# octanis_v0_6.net
KiCad netlist of a schematic drawn in EAGLE
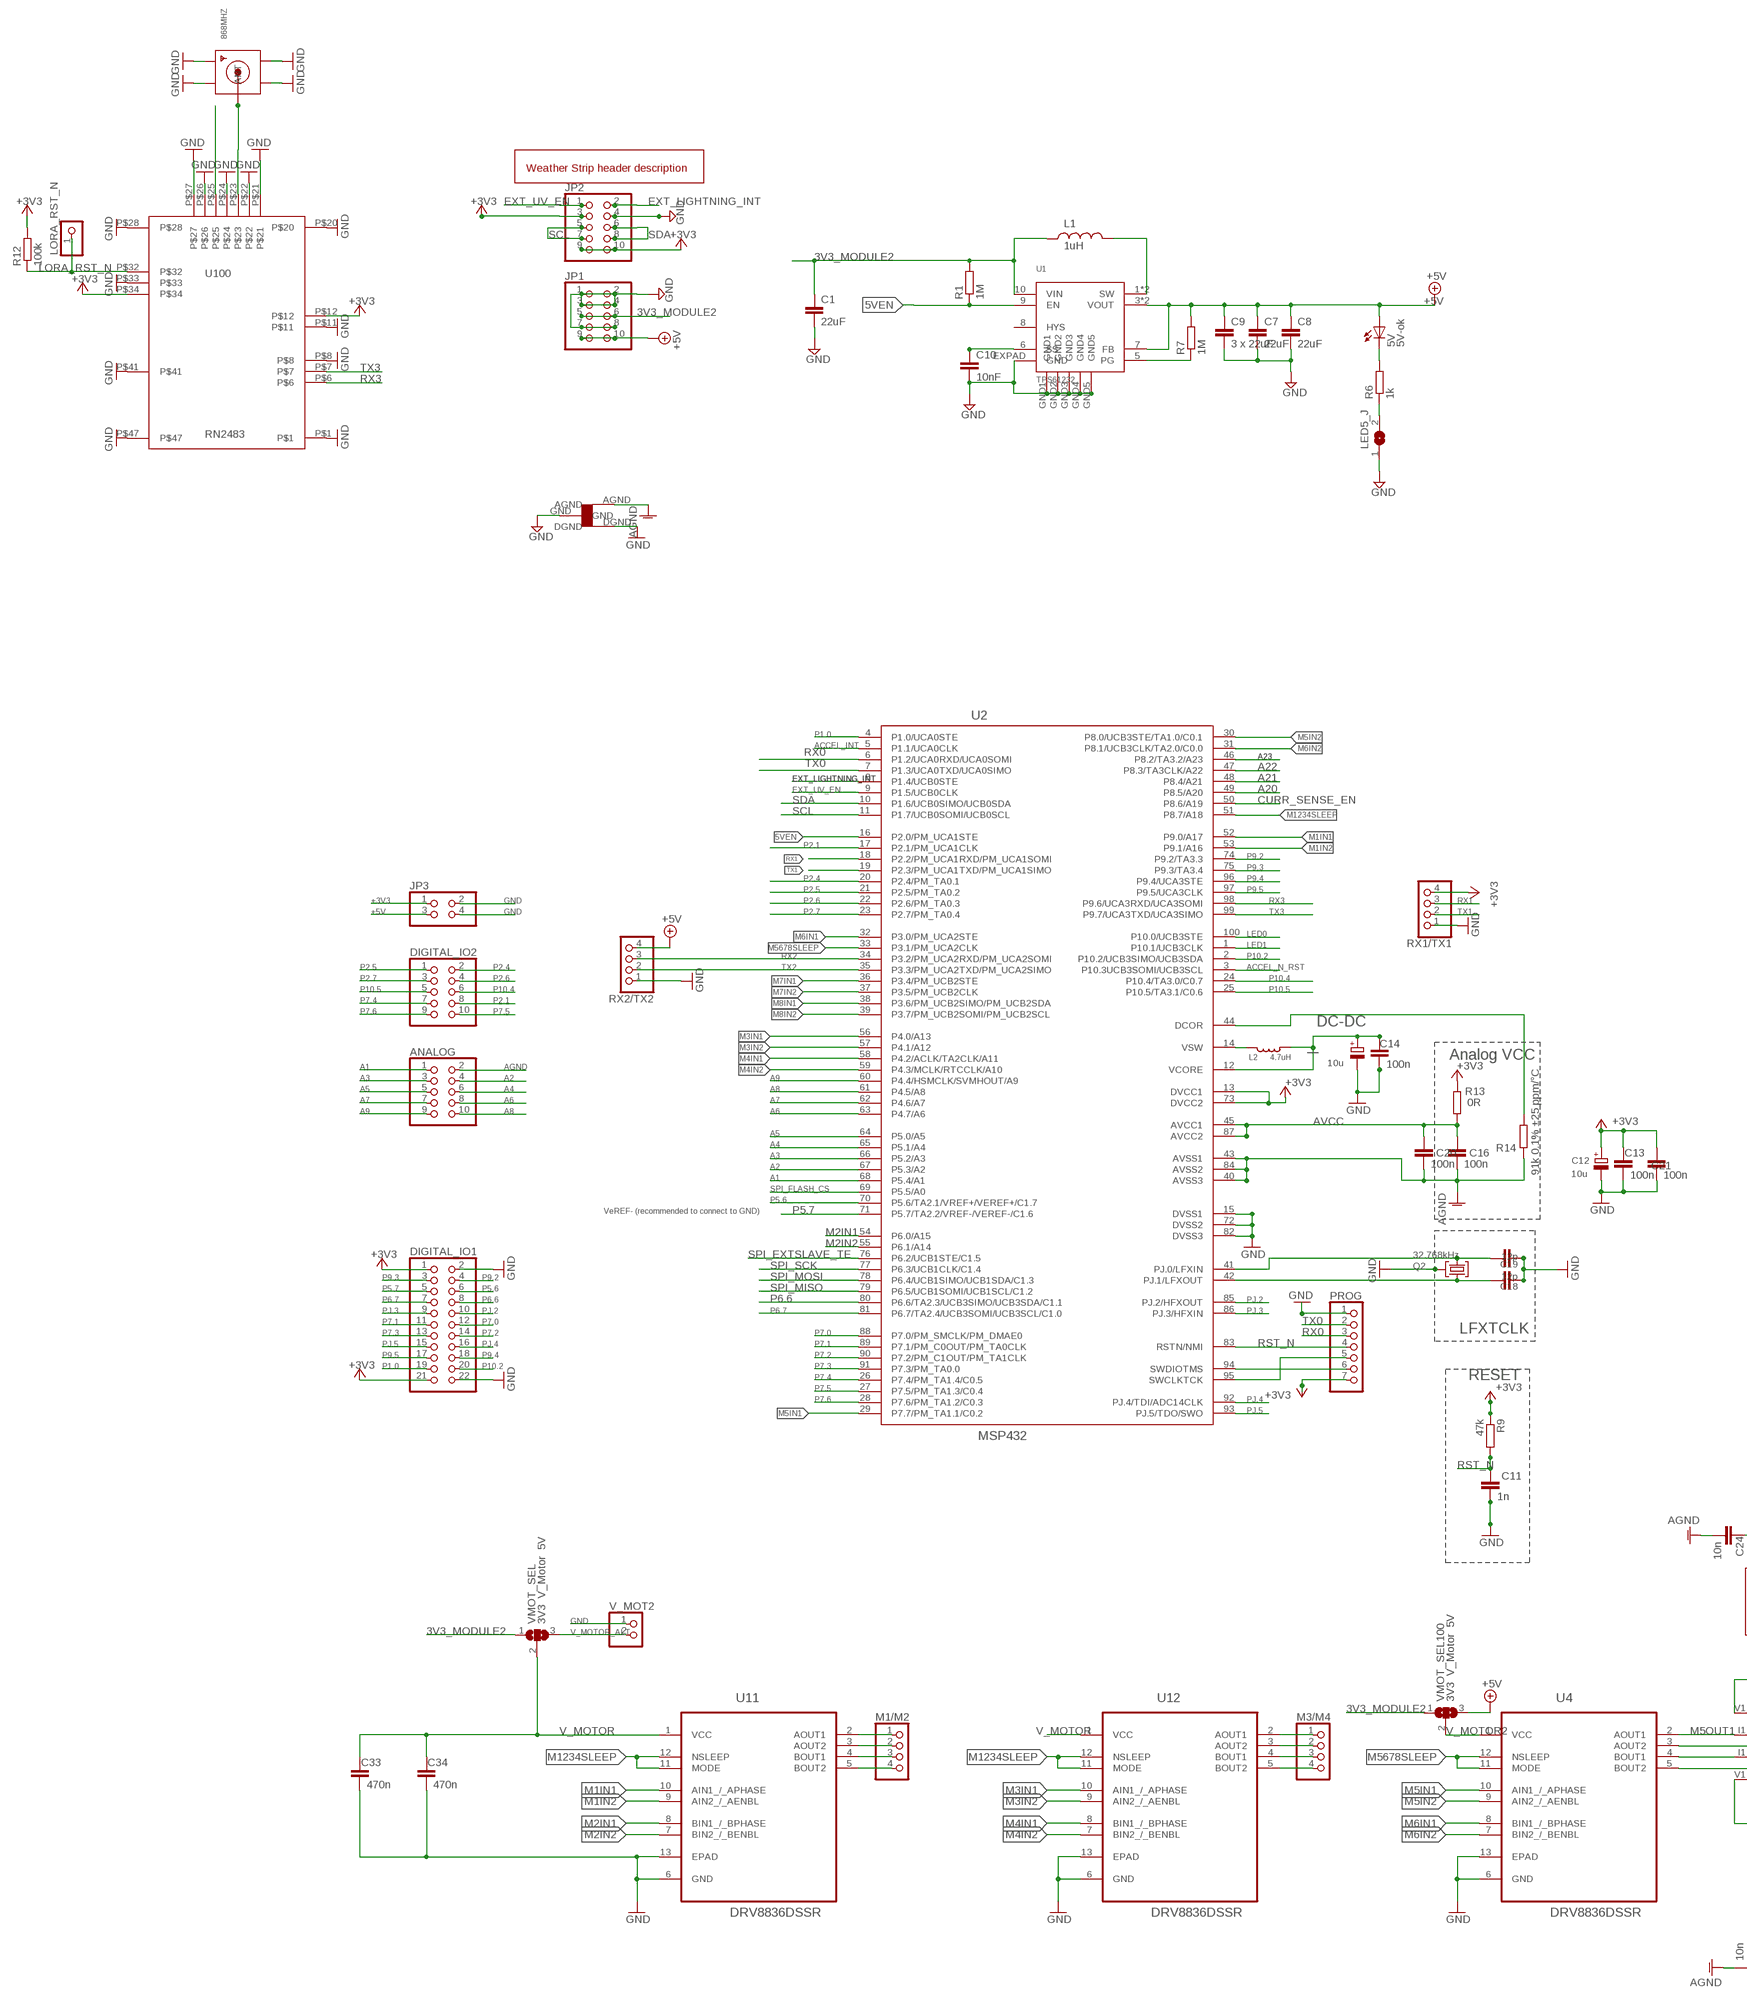
[diagram p0: schematic, sheet 1, part 1 of 2]
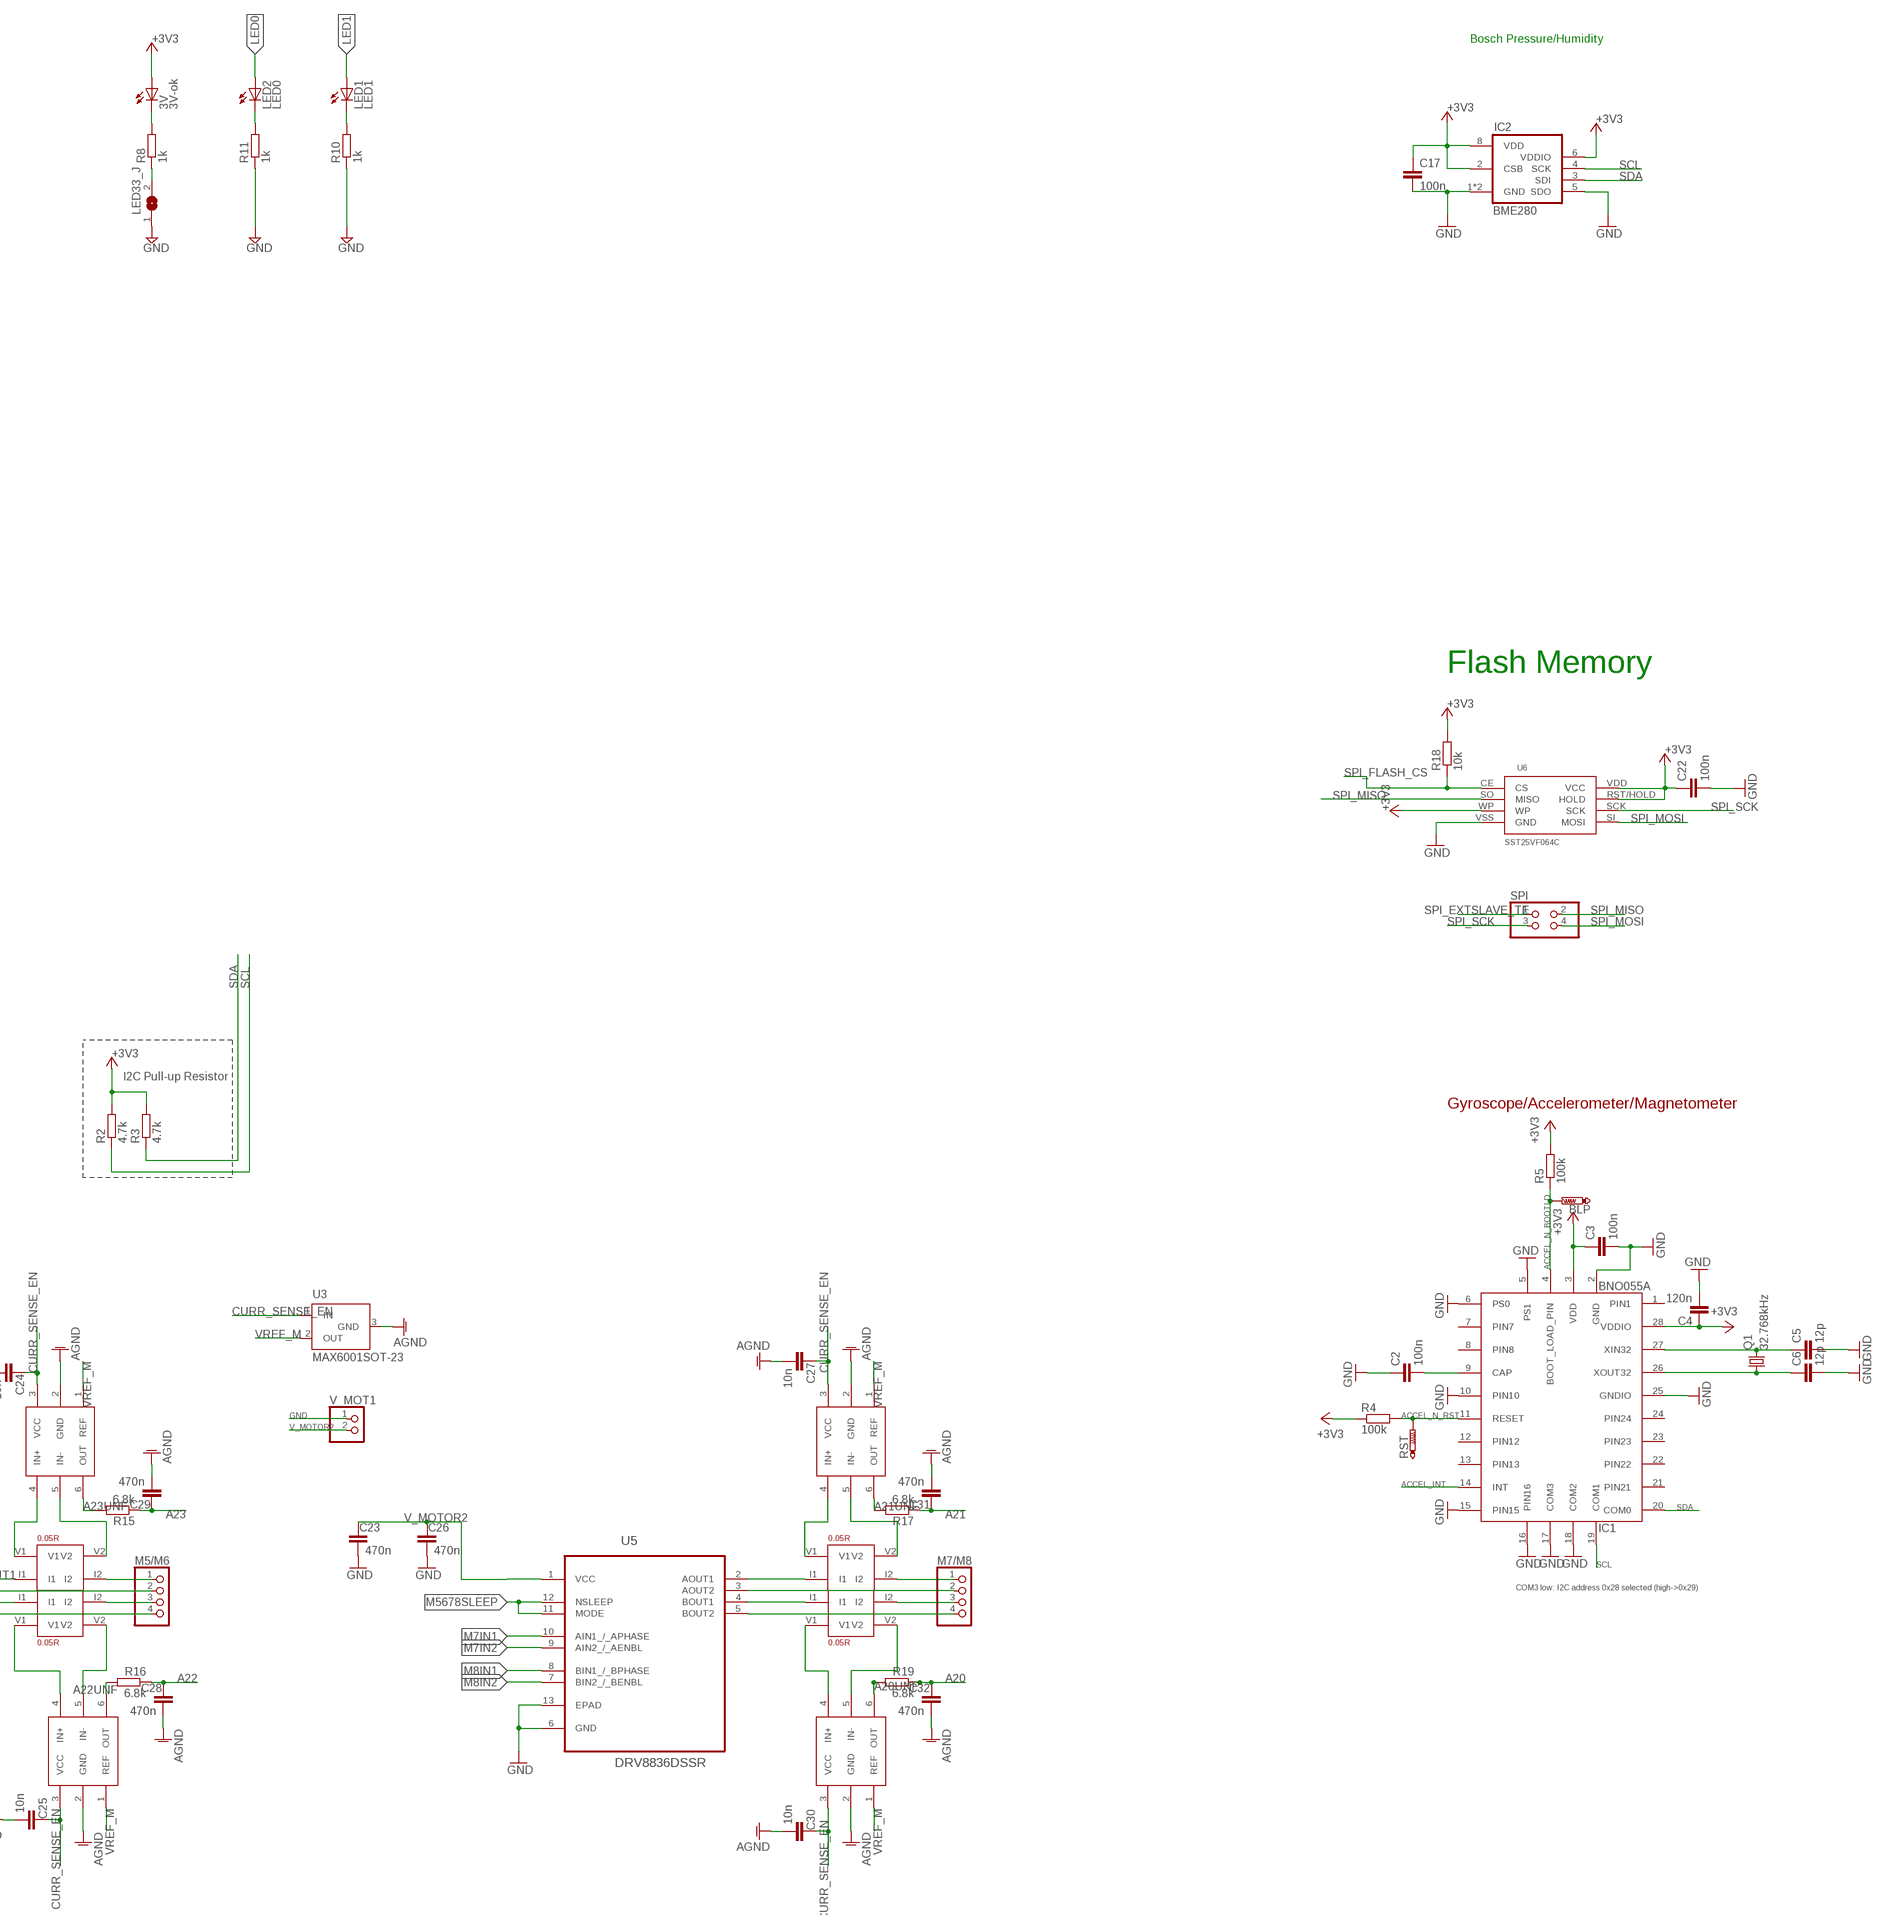
[diagram p1: schematic, sheet 1, part 2 of 2]

(export (version "E")
  (design (tool "Eeschema 10.0.6"))
  (components
    (comp (ref "3V")
      (value "3V-ok")
      (footprint "eagle-import:CHIPLED_0603")
      (libsource (lib "eagle-import") (part "LEDCHIPLED_0603"))
    )
    (comp (ref "5V")
      (value "5V-ok")
      (footprint "eagle-import:CHIPLED_0603")
      (libsource (lib "eagle-import") (part "LEDCHIPLED_0603"))
    )
    (comp (ref "868MHZ")
      (value "SMACONNECTOR_EDGE")
      (footprint "eagle-import:SMA_EDGELAUNCH")
      (libsource (lib "eagle-import") (part "SMACONNECTOR_EDGE"))
    )
    (comp (ref "ANALOG")
      (value "PINHD-2X5")
      (footprint "eagle-import:2X05")
      (libsource (lib "eagle-import") (part "PINHD-2X5"))
    )
    (comp (ref "BLP")
      (value "PTR1B1,27")
      (footprint "eagle-import:B1,27")
      (libsource (lib "eagle-import") (part "PTR1B1,27"))
    )
    (comp (ref "C1")
      (value "22uF")
      (footprint "eagle-import:C0603")
      (libsource (lib "eagle-import") (part "C-EUC0603"))
    )
    (comp (ref "C2")
      (value "100n")
      (footprint "eagle-import:C0603")
      (libsource (lib "eagle-import") (part "C-EUC0603"))
    )
    (comp (ref "C3")
      (value "100n")
      (footprint "eagle-import:C0603")
      (libsource (lib "eagle-import") (part "C-EUC0603"))
    )
    (comp (ref "C4")
      (value "120n")
      (footprint "eagle-import:C0603")
      (libsource (lib "eagle-import") (part "C-EUC0603"))
    )
    (comp (ref "C5")
      (value "12p")
      (footprint "eagle-import:C0603")
      (libsource (lib "eagle-import") (part "C-EUC0603"))
    )
    (comp (ref "C6")
      (value "12p")
      (footprint "eagle-import:C0603")
      (libsource (lib "eagle-import") (part "C-EUC0603"))
    )
    (comp (ref "C7")
      (value "22uF")
      (footprint "eagle-import:C0603")
      (libsource (lib "eagle-import") (part "C-EUC0603"))
    )
    (comp (ref "C8")
      (value "22uF")
      (footprint "eagle-import:C0603")
      (libsource (lib "eagle-import") (part "C-EUC0603"))
    )
    (comp (ref "C9")
      (value "3 x 22uF")
      (footprint "eagle-import:C0603")
      (libsource (lib "eagle-import") (part "C-EUC0603"))
    )
    (comp (ref "C10")
      (value "10nF")
      (footprint "eagle-import:C0603")
      (libsource (lib "eagle-import") (part "C-EUC0603"))
    )
    (comp (ref "C11")
      (value "1n")
      (footprint "eagle-import:C0603")
      (libsource (lib "eagle-import") (part "C-EUC0603"))
    )
    (comp (ref "C12")
      (value "10u")
      (footprint "eagle-import:A_3216-18R")
      (libsource (lib "eagle-import") (part "CPOL-EUA/3216-18R"))
    )
    (comp (ref "C13")
      (value "100n")
      (footprint "eagle-import:C0603")
      (libsource (lib "eagle-import") (part "C-EUC0603"))
    )
    (comp (ref "C14")
      (value "100n")
      (footprint "eagle-import:C0603")
      (libsource (lib "eagle-import") (part "C-EUC0603"))
    )
    (comp (ref "C15")
      (value "10u")
      (footprint "eagle-import:A_3216-18R")
      (libsource (lib "eagle-import") (part "CPOL-EUA/3216-18R"))
    )
    (comp (ref "C16")
      (value "100n")
      (footprint "eagle-import:C0402")
      (libsource (lib "eagle-import") (part "C-EUC0402"))
    )
    (comp (ref "C17")
      (value "100n")
      (footprint "eagle-import:C0603")
      (libsource (lib "eagle-import") (part "C-EUC0603"))
    )
    (comp (ref "C18")
      (value "12p")
      (footprint "eagle-import:C0402")
      (libsource (lib "eagle-import") (part "C-EUC0402"))
    )
    (comp (ref "C19")
      (value "12p")
      (footprint "eagle-import:C0402")
      (libsource (lib "eagle-import") (part "C-EUC0402"))
    )
    (comp (ref "C20")
      (value "100n")
      (footprint "eagle-import:C0402")
      (libsource (lib "eagle-import") (part "C-EUC0402"))
    )
    (comp (ref "C21")
      (value "100n")
      (footprint "eagle-import:C0603")
      (libsource (lib "eagle-import") (part "C-EUC0603"))
    )
    (comp (ref "C22")
      (value "100n")
      (footprint "eagle-import:C0603")
      (libsource (lib "eagle-import") (part "C-EUC0603"))
    )
    (comp (ref "C23")
      (value "470n")
      (footprint "eagle-import:C0603")
      (libsource (lib "eagle-import") (part "C-EUC0603"))
    )
    (comp (ref "C24")
      (value "10n")
      (footprint "eagle-import:C0603")
      (libsource (lib "eagle-import") (part "C-EUC0603"))
    )
    (comp (ref "C25")
      (value "10n")
      (footprint "eagle-import:C0603")
      (libsource (lib "eagle-import") (part "C-EUC0603"))
    )
    (comp (ref "C26")
      (value "470n")
      (footprint "eagle-import:C0603")
      (libsource (lib "eagle-import") (part "C-EUC0603"))
    )
    (comp (ref "C27")
      (value "10n")
      (footprint "eagle-import:C0603")
      (libsource (lib "eagle-import") (part "C-EUC0603"))
    )
    (comp (ref "C28")
      (value "470n")
      (footprint "eagle-import:C0603")
      (libsource (lib "eagle-import") (part "C-EUC0603"))
    )
    (comp (ref "C29")
      (value "470n")
      (footprint "eagle-import:C0603")
      (libsource (lib "eagle-import") (part "C-EUC0603"))
    )
    (comp (ref "C30")
      (value "10n")
      (footprint "eagle-import:C0603")
      (libsource (lib "eagle-import") (part "C-EUC0603"))
    )
    (comp (ref "C31")
      (value "470n")
      (footprint "eagle-import:C0603")
      (libsource (lib "eagle-import") (part "C-EUC0603"))
    )
    (comp (ref "C32")
      (value "470n")
      (footprint "eagle-import:C0603")
      (libsource (lib "eagle-import") (part "C-EUC0603"))
    )
    (comp (ref "C33")
      (value "470n")
      (footprint "eagle-import:C0603")
      (libsource (lib "eagle-import") (part "C-EUC0603"))
    )
    (comp (ref "C34")
      (value "470n")
      (footprint "eagle-import:C0603")
      (libsource (lib "eagle-import") (part "C-EUC0603"))
    )
    (comp (ref "DIGITAL_IO1")
      (value "PINHD-2X11")
      (footprint "eagle-import:2X11")
      (libsource (lib "eagle-import") (part "PINHD-2X11"))
    )
    (comp (ref "DIGITAL_IO2")
      (value "PINHD-2X5")
      (footprint "eagle-import:2X05")
      (libsource (lib "eagle-import") (part "PINHD-2X5"))
    )
    (comp (ref "IC1")
      (value "BNO055A")
      (footprint "eagle-import:BNO055")
      (libsource (lib "eagle-import") (part "BNO055A"))
    )
    (comp (ref "IC2")
      (value "BME280")
      (footprint "eagle-import:BME280")
      (libsource (lib "eagle-import") (part "BME280"))
    )
    (comp (ref "JP1")
      (value "PINHD-2X05_2.54")
      (footprint "eagle-import:2X05")
      (libsource (lib "eagle-import") (part "PINHD-2X05_2.54"))
    )
    (comp (ref "JP2")
      (value "PINHD-2X05_2.54-SMD")
      (footprint "eagle-import:2X05SMD")
      (libsource (lib "eagle-import") (part "PINHD-2X05_2.54-SMD"))
    )
    (comp (ref "JP3")
      (value "PINHD-2X2")
      (footprint "eagle-import:2X02")
      (libsource (lib "eagle-import") (part "PINHD-2X2"))
    )
    (comp (ref "L1")
      (value "1uH")
      (footprint "eagle-import:XFL4020")
      (libsource (lib "eagle-import") (part "XFL4020"))
    )
    (comp (ref "L2")
      (value "4.7uH")
      (footprint "eagle-import:0806")
      (libsource (lib "eagle-import") (part "LQM2MP_G0"))
    )
    (comp (ref "LED1")
      (value "LED1")
      (footprint "eagle-import:CHIPLED_0603")
      (libsource (lib "eagle-import") (part "LEDCHIPLED_0603"))
    )
    (comp (ref "LED2")
      (value "LED0")
      (footprint "eagle-import:CHIPLED_0603")
      (libsource (lib "eagle-import") (part "LEDCHIPLED_0603"))
    )
    (comp (ref "LED5_J")
      (value "SJ")
      (footprint "eagle-import:SJ")
      (libsource (lib "eagle-import") (part "SJ"))
    )
    (comp (ref "LED33_J")
      (value "SJ")
      (footprint "eagle-import:SJ")
      (libsource (lib "eagle-import") (part "SJ"))
    )
    (comp (ref "LORA_RST_N")
      (value "PINHD-1X1")
      (footprint "eagle-import:1X01")
      (libsource (lib "eagle-import") (part "PINHD-1X1"))
    )
    (comp (ref "M1/M2")
      (value "PINHD-1X04_2.54-S")
      (footprint "eagle-import:1X04-S")
      (libsource (lib "eagle-import") (part "PINHD-1X04_2.54-S"))
    )
    (comp (ref "M3/M4")
      (value "PINHD-1X04_2.54-S")
      (footprint "eagle-import:1X04-S")
      (libsource (lib "eagle-import") (part "PINHD-1X04_2.54-S"))
    )
    (comp (ref "M5/M6")
      (value "PINHD-1X04_2.54-S")
      (footprint "eagle-import:1X04-S")
      (libsource (lib "eagle-import") (part "PINHD-1X04_2.54-S"))
    )
    (comp (ref "M7/M8")
      (value "PINHD-1X04_2.54-S")
      (footprint "eagle-import:1X04-S")
      (libsource (lib "eagle-import") (part "PINHD-1X04_2.54-S"))
    )
    (comp (ref "PROG")
      (value "PINHD-1X72MM_SMD")
      (footprint "eagle-import:1X7SMD")
      (libsource (lib "eagle-import") (part "PINHD-1X72MM_SMD"))
    )
    (comp (ref "Q1")
      (value "32.768kHz")
      (footprint "eagle-import:FC-12M")
      (libsource (lib "eagle-import") (part "FC-12M"))
    )
    (comp (ref "Q2")
      (value "32.768kHz")
      (footprint "eagle-import:MS3V-T1R")
      (libsource (lib "eagle-import") (part "MS3V-T1R"))
    )
    (comp (ref "R1")
      (value "1M")
      (footprint "eagle-import:R0603")
      (libsource (lib "eagle-import") (part "R-EU_R0603"))
    )
    (comp (ref "R2")
      (value "4.7k")
      (footprint "eagle-import:R0603")
      (libsource (lib "eagle-import") (part "R-EU_R0603"))
    )
    (comp (ref "R3")
      (value "4.7k")
      (footprint "eagle-import:R0603")
      (libsource (lib "eagle-import") (part "R-EU_R0603"))
    )
    (comp (ref "R4")
      (value "100k")
      (footprint "eagle-import:R0603")
      (libsource (lib "eagle-import") (part "R-EU_R0603"))
    )
    (comp (ref "R5")
      (value "100k")
      (footprint "eagle-import:R0603")
      (libsource (lib "eagle-import") (part "R-EU_R0603"))
    )
    (comp (ref "R6")
      (value "1k")
      (footprint "eagle-import:R0603")
      (libsource (lib "eagle-import") (part "R-EU_R0603"))
    )
    (comp (ref "R7")
      (value "1M")
      (footprint "eagle-import:R0603")
      (libsource (lib "eagle-import") (part "R-EU_R0603"))
    )
    (comp (ref "R8")
      (value "1k")
      (footprint "eagle-import:R0603")
      (libsource (lib "eagle-import") (part "R-EU_R0603"))
    )
    (comp (ref "R9")
      (value "47k")
      (footprint "eagle-import:R0603")
      (libsource (lib "eagle-import") (part "R-EU_R0603"))
    )
    (comp (ref "R10")
      (value "1k")
      (footprint "eagle-import:R0603")
      (libsource (lib "eagle-import") (part "R-EU_R0603"))
    )
    (comp (ref "R11")
      (value "1k")
      (footprint "eagle-import:R0603")
      (libsource (lib "eagle-import") (part "R-EU_R0603"))
    )
    (comp (ref "R12")
      (value "100k")
      (footprint "eagle-import:R0603")
      (libsource (lib "eagle-import") (part "R-EU_R0603"))
    )
    (comp (ref "R13")
      (value "0R")
      (footprint "eagle-import:R0402")
      (libsource (lib "eagle-import") (part "R-EU_R0402"))
    )
    (comp (ref "R14")
      (value "91k 0.1% ±25 ppm/°C")
      (footprint "eagle-import:R0402")
      (libsource (lib "eagle-import") (part "R-EU_R0402"))
    )
    (comp (ref "R15")
      (value "6.8k")
      (footprint "eagle-import:R0603")
      (libsource (lib "eagle-import") (part "R-EU_R0603"))
    )
    (comp (ref "R16")
      (value "6.8k")
      (footprint "eagle-import:R0603")
      (libsource (lib "eagle-import") (part "R-EU_R0603"))
    )
    (comp (ref "R17")
      (value "6.8k")
      (footprint "eagle-import:R0603")
      (libsource (lib "eagle-import") (part "R-EU_R0603"))
    )
    (comp (ref "R18")
      (value "10k")
      (footprint "eagle-import:R0603")
      (libsource (lib "eagle-import") (part "R-EU_R0603"))
    )
    (comp (ref "R19")
      (value "6.8k")
      (footprint "eagle-import:R0603")
      (libsource (lib "eagle-import") (part "R-EU_R0603"))
    )
    (comp (ref "RS1")
      (value "0.05R")
      (footprint "eagle-import:4PADS_RESISTOR")
      (libsource (lib "eagle-import") (part "CURRENT_RESISTOR"))
    )
    (comp (ref "RS2")
      (value "0.05R")
      (footprint "eagle-import:4PADS_RESISTOR")
      (libsource (lib "eagle-import") (part "CURRENT_RESISTOR"))
    )
    (comp (ref "RS3")
      (value "0.05R")
      (footprint "eagle-import:4PADS_RESISTOR")
      (libsource (lib "eagle-import") (part "CURRENT_RESISTOR"))
    )
    (comp (ref "RS4")
      (value "0.05R")
      (footprint "eagle-import:4PADS_RESISTOR")
      (libsource (lib "eagle-import") (part "CURRENT_RESISTOR"))
    )
    (comp (ref "RST")
      (value "PTR1B1,27")
      (footprint "eagle-import:B1,27")
      (libsource (lib "eagle-import") (part "PTR1B1,27"))
    )
    (comp (ref "RX1/TX1")
      (value "PINHD-1X04_2.54-S")
      (footprint "eagle-import:1X04-S")
      (libsource (lib "eagle-import") (part "PINHD-1X04_2.54-S"))
    )
    (comp (ref "RX2/TX2")
      (value "PINHD-1X04_2.54-S")
      (footprint "eagle-import:1X04-S")
      (libsource (lib "eagle-import") (part "PINHD-1X04_2.54-S"))
    )
    (comp (ref "SPI")
      (value "PINHD-2X2")
      (footprint "eagle-import:2X02")
      (libsource (lib "eagle-import") (part "PINHD-2X2"))
    )
    (comp (ref "U$1")
      (value "WEATHER_STRIP_DOCU")
      (footprint "eagle-import:WEATHER_STRIP_DOCU")
      (libsource (lib "eagle-import") (part "WEATHER_STRIP_DOCU"))
    )
    (comp (ref "U$2")
      (value "STARGND")
      (footprint "eagle-import:STAR")
      (libsource (lib "eagle-import") (part "STARGND"))
    )
    (comp (ref "U1")
      (value "TPS61232")
      (footprint "eagle-import:S-PVSON-N10")
      (libsource (lib "eagle-import") (part "TPS61232"))
    )
    (comp (ref "U2")
      (value "MSP432")
      (footprint "eagle-import:PZ100")
      (libsource (lib "eagle-import") (part "MSP432"))
    )
    (comp (ref "U3")
      (value "MAX6001SOT-23")
      (footprint "eagle-import:MAX6001")
      (libsource (lib "eagle-import") (part "MAX6001SOT-23"))
    )
    (comp (ref "U4")
      (value "DRV8836DSSR")
      (footprint "eagle-import:SON50P200X300X80-13N")
      (fields (field (name "MPN") "DRV8836DSSR "))
      (libsource (lib "eagle-import") (part "DRV8836DSSR"))
    )
    (comp (ref "U5")
      (value "DRV8836DSSR")
      (footprint "eagle-import:SON50P200X300X80-13N")
      (fields (field (name "MPN") "DRV8836DSSR "))
      (libsource (lib "eagle-import") (part "DRV8836DSSR"))
    )
    (comp (ref "U6")
      (value "SST25VF064C")
      (footprint "eagle-import:SOIC_8-LEAD")
      (libsource (lib "eagle-import") (part "SST25VF064C"))
    )
    (comp (ref "U7")
      (value "INA210")
      (footprint "eagle-import:SC70-6")
      (libsource (lib "eagle-import") (part "INA213"))
    )
    (comp (ref "U8")
      (value "INA210")
      (footprint "eagle-import:SC70-6")
      (libsource (lib "eagle-import") (part "INA213"))
    )
    (comp (ref "U9")
      (value "INA210")
      (footprint "eagle-import:SC70-6")
      (libsource (lib "eagle-import") (part "INA213"))
    )
    (comp (ref "U10")
      (value "INA210")
      (footprint "eagle-import:SC70-6")
      (libsource (lib "eagle-import") (part "INA213"))
    )
    (comp (ref "U11")
      (value "DRV8836DSSR")
      (footprint "eagle-import:SON50P200X300X80-13N")
      (fields (field (name "MPN") "DRV8836DSSR "))
      (libsource (lib "eagle-import") (part "DRV8836DSSR"))
    )
    (comp (ref "U12")
      (value "DRV8836DSSR")
      (footprint "eagle-import:SON50P200X300X80-13N")
      (fields (field (name "MPN") "DRV8836DSSR "))
      (libsource (lib "eagle-import") (part "DRV8836DSSR"))
    )
    (comp (ref "U100")
      (value "RN2483")
      (footprint "eagle-import:RN2483")
      (libsource (lib "eagle-import") (part "RN2483"))
    )
    (comp (ref "VMOT_SEL")
      (value "3V3 V_Motor 5V")
      (footprint "eagle-import:SJ_2")
      (libsource (lib "eagle-import") (part "SJ2W"))
    )
    (comp (ref "VMOT_SEL100")
      (value "3V3 V_Motor 5V")
      (footprint "eagle-import:SJ_2")
      (libsource (lib "eagle-import") (part "SJ2W"))
    )
    (comp (ref "V_MOT1")
      (value "PINHD-1X02_2.54-S")
      (footprint "eagle-import:1X02-S")
      (libsource (lib "eagle-import") (part "PINHD-1X02_2.54-S"))
    )
    (comp (ref "V_MOT2")
      (value "PINHD-1X02_2.54-S")
      (footprint "eagle-import:1X02-S")
      (libsource (lib "eagle-import") (part "PINHD-1X02_2.54-S"))
    )
  )
  (nets
    (net (code "1") (name "+3V3") (class "Default")
      (node (ref "3V") (pin "A") (pinfunction "A_A") (pintype "passive"))
      (node (ref "C12") (pin "+") (pinfunction "+_+") (pintype "passive"))
      (node (ref "C13") (pin "2") (pinfunction "2_2") (pintype "passive"))
      (node (ref "C17") (pin "1") (pinfunction "1_1") (pintype "passive"))
      (node (ref "C21") (pin "2") (pinfunction "2_2") (pintype "passive"))
      (node (ref "C22") (pin "1") (pinfunction "1_1") (pintype "passive"))
      (node (ref "C3") (pin "1") (pinfunction "1_1") (pintype "passive"))
      (node (ref "C4") (pin "1") (pinfunction "1_1") (pintype "passive"))
      (node (ref "DIGITAL_IO1") (pin "1") (pinfunction "1_1") (pintype "passive"))
      (node (ref "DIGITAL_IO1") (pin "21") (pinfunction "21_21") (pintype "passive"))
      (node (ref "IC1") (pin "28") (pinfunction "VDDIO_28") (pintype "bidirectional"))
      (node (ref "IC1") (pin "3") (pinfunction "VDD_3") (pintype "bidirectional"))
      (node (ref "IC2") (pin "2") (pinfunction "CSB_2") (pintype "input"))
      (node (ref "IC2") (pin "6") (pinfunction "VDDIO_6") (pintype "power_in"))
      (node (ref "IC2") (pin "8") (pinfunction "VDD_8") (pintype "power_in"))
      (node (ref "JP2") (pin "10") (pinfunction "10_10") (pintype "passive"))
      (node (ref "JP2") (pin "3") (pinfunction "3_3") (pintype "passive"))
      (node (ref "JP2") (pin "9") (pinfunction "9_9") (pintype "passive"))
      (node (ref "JP3") (pin "1") (pinfunction "1_1") (pintype "passive"))
      (node (ref "PROG") (pin "7") (pinfunction "7_7") (pintype "passive"))
      (node (ref "R12") (pin "2") (pinfunction "2_2") (pintype "passive"))
      (node (ref "R13") (pin "2") (pinfunction "2_2") (pintype "passive"))
      (node (ref "R18") (pin "2") (pinfunction "2_2") (pintype "passive"))
      (node (ref "R2") (pin "2") (pinfunction "2_2") (pintype "passive"))
      (node (ref "R3") (pin "2") (pinfunction "2_2") (pintype "passive"))
      (node (ref "R4") (pin "1") (pinfunction "1_1") (pintype "passive"))
      (node (ref "R5") (pin "2") (pinfunction "2_2") (pintype "passive"))
      (node (ref "R9") (pin "1") (pinfunction "1_1") (pintype "passive"))
      (node (ref "RX1/TX1") (pin "4") (pinfunction "4_4") (pintype "passive"))
      (node (ref "U100") (pin "P$12") (pinfunction "P$12_P$12") (pintype "bidirectional"))
      (node (ref "U100") (pin "P$34") (pinfunction "P$34_P$34") (pintype "bidirectional"))
      (node (ref "U2") (pin "13") (pinfunction "DVCC1_13") (pintype "power_in"))
      (node (ref "U2") (pin "73") (pinfunction "DVCC2_73") (pintype "power_in"))
      (node (ref "U6") (pin "RST/HOLD") (pinfunction "HOLD_RST/HOLD") (pintype "bidirectional"))
      (node (ref "U6") (pin "VDD") (pinfunction "VCC_VDD") (pintype "bidirectional"))
      (node (ref "U6") (pin "WP") (pinfunction "WP_WP") (pintype "bidirectional"))
    )
    (net (code "2") (name "+5V") (class "Default")
      (node (ref "5V") (pin "A") (pinfunction "A_A") (pintype "passive"))
      (node (ref "C7") (pin "1") (pinfunction "1_1") (pintype "passive"))
      (node (ref "C8") (pin "1") (pinfunction "1_1") (pintype "passive"))
      (node (ref "C9") (pin "1") (pinfunction "1_1") (pintype "passive"))
      (node (ref "JP1") (pin "10") (pinfunction "10_10") (pintype "passive"))
      (node (ref "JP1") (pin "9") (pinfunction "9_9") (pintype "passive"))
      (node (ref "JP3") (pin "3") (pinfunction "3_3") (pintype "passive"))
      (node (ref "R7") (pin "2") (pinfunction "2_2") (pintype "passive"))
      (node (ref "RX2/TX2") (pin "4") (pinfunction "4_4") (pintype "passive"))
      (node (ref "U1") (pin "3") (pinfunction "VOUT_3") (pintype "power_in"))
      (node (ref "U1") (pin "4") (pinfunction "VOUT_4") (pintype "power_in"))
      (node (ref "U1") (pin "7") (pinfunction "FB_7") (pintype "input"))
      (node (ref "VMOT_SEL100") (pin "3") (pinfunction "3_3") (pintype "passive"))
    )
    (net (code "3") (name "/3V3_MODULE2") (class "Default")
      (node (ref "C1") (pin "1") (pinfunction "1_1") (pintype "passive"))
      (node (ref "JP1") (pin "5") (pinfunction "5_5") (pintype "passive"))
      (node (ref "JP1") (pin "6") (pinfunction "6_6") (pintype "passive"))
      (node (ref "L1") (pin "P$1") (pinfunction "1_P$1") (pintype "passive"))
      (node (ref "R1") (pin "2") (pinfunction "2_2") (pintype "passive"))
      (node (ref "U1") (pin "10") (pinfunction "VIN_10") (pintype "input"))
      (node (ref "VMOT_SEL") (pin "1") (pinfunction "1_1") (pintype "passive"))
      (node (ref "VMOT_SEL100") (pin "1") (pinfunction "1_1") (pintype "passive"))
    )
    (net (code "4") (name "/A1") (class "Default")
      (node (ref "ANALOG") (pin "1") (pinfunction "1_1") (pintype "passive"))
      (node (ref "U2") (pin "68") (pinfunction "P5.4/A1_68") (pintype "power_in"))
    )
    (net (code "5") (name "/A2") (class "Default")
      (node (ref "ANALOG") (pin "4") (pinfunction "4_4") (pintype "passive"))
      (node (ref "U2") (pin "67") (pinfunction "P5.3/A2_67") (pintype "power_in"))
    )
    (net (code "6") (name "/A3") (class "Default")
      (node (ref "ANALOG") (pin "3") (pinfunction "3_3") (pintype "passive"))
      (node (ref "U2") (pin "66") (pinfunction "P5.2/A3_66") (pintype "power_in"))
    )
    (net (code "7") (name "/A4") (class "Default")
      (node (ref "ANALOG") (pin "6") (pinfunction "6_6") (pintype "passive"))
      (node (ref "U2") (pin "65") (pinfunction "P5.1/A4_65") (pintype "power_in"))
    )
    (net (code "8") (name "/A5") (class "Default")
      (node (ref "ANALOG") (pin "5") (pinfunction "5_5") (pintype "passive"))
      (node (ref "U2") (pin "64") (pinfunction "P5.0/A5_64") (pintype "power_in"))
    )
    (net (code "9") (name "/A6") (class "Default")
      (node (ref "ANALOG") (pin "8") (pinfunction "8_8") (pintype "passive"))
      (node (ref "U2") (pin "63") (pinfunction "P4.7/A6_63") (pintype "power_in"))
    )
    (net (code "10") (name "/A7") (class "Default")
      (node (ref "ANALOG") (pin "7") (pinfunction "7_7") (pintype "passive"))
      (node (ref "U2") (pin "62") (pinfunction "P4.6/A7_62") (pintype "power_in"))
    )
    (net (code "11") (name "/A8") (class "Default")
      (node (ref "ANALOG") (pin "10") (pinfunction "10_10") (pintype "passive"))
      (node (ref "U2") (pin "61") (pinfunction "P4.5/A8_61") (pintype "power_in"))
    )
    (net (code "12") (name "/A9") (class "Default")
      (node (ref "ANALOG") (pin "9") (pinfunction "9_9") (pintype "passive"))
      (node (ref "U2") (pin "60") (pinfunction "P4.4/HSMCLK/SVMHOUT/A9_60") (pintype "power_in"))
    )
    (net (code "13") (name "/A20") (class "Default")
      (node (ref "C32") (pin "2") (pinfunction "2_2") (pintype "passive"))
      (node (ref "R19") (pin "1") (pinfunction "1_1") (pintype "passive"))
      (node (ref "U2") (pin "49") (pinfunction "P8.5/A20_49") (pintype "power_in"))
    )
    (net (code "14") (name "/A20UNF") (class "Default")
      (node (ref "R19") (pin "2") (pinfunction "2_2") (pintype "passive"))
      (node (ref "U10") (pin "6") (pinfunction "OUT_6") (pintype "bidirectional"))
    )
    (net (code "15") (name "/A21") (class "Default")
      (node (ref "C31") (pin "2") (pinfunction "2_2") (pintype "passive"))
      (node (ref "R17") (pin "1") (pinfunction "1_1") (pintype "passive"))
      (node (ref "U2") (pin "48") (pinfunction "P8.4/A21_48") (pintype "power_in"))
    )
    (net (code "16") (name "/A21UNF") (class "Default")
      (node (ref "R17") (pin "2") (pinfunction "2_2") (pintype "passive"))
      (node (ref "U9") (pin "6") (pinfunction "OUT_6") (pintype "bidirectional"))
    )
    (net (code "17") (name "/A22") (class "Default")
      (node (ref "C28") (pin "2") (pinfunction "2_2") (pintype "passive"))
      (node (ref "R16") (pin "1") (pinfunction "1_1") (pintype "passive"))
      (node (ref "U2") (pin "47") (pinfunction "P8.3/TA3CLK/A22_47") (pintype "power_in"))
    )
    (net (code "18") (name "/A22UNF") (class "Default")
      (node (ref "R16") (pin "2") (pinfunction "2_2") (pintype "passive"))
      (node (ref "U8") (pin "6") (pinfunction "OUT_6") (pintype "bidirectional"))
    )
    (net (code "19") (name "/A23") (class "Default")
      (node (ref "C29") (pin "2") (pinfunction "2_2") (pintype "passive"))
      (node (ref "R15") (pin "1") (pinfunction "1_1") (pintype "passive"))
      (node (ref "U2") (pin "46") (pinfunction "P8.2/TA3.2/A23_46") (pintype "power_in"))
    )
    (net (code "20") (name "/A23UNF") (class "Default")
      (node (ref "R15") (pin "2") (pinfunction "2_2") (pintype "passive"))
      (node (ref "U7") (pin "6") (pinfunction "OUT_6") (pintype "bidirectional"))
    )
    (net (code "21") (name "/ACCEL_INT") (class "Default")
      (node (ref "IC1") (pin "14") (pinfunction "INT_14") (pintype "bidirectional"))
      (node (ref "U2") (pin "5") (pinfunction "P1.1/UCA0CLK_5") (pintype "power_in"))
    )
    (net (code "22") (name "/ACCEL_N_BOOTLD") (class "Default")
      (node (ref "BLP") (pin "TP") (pinfunction "TP_TP") (pintype "input"))
      (node (ref "IC1") (pin "4") (pinfunction "BOOT_LOAD_PIN_4") (pintype "bidirectional"))
      (node (ref "R5") (pin "1") (pinfunction "1_1") (pintype "passive"))
    )
    (net (code "23") (name "/ACCEL_N_RST") (class "Default")
      (node (ref "IC1") (pin "11") (pinfunction "RESET_11") (pintype "bidirectional"))
      (node (ref "R4") (pin "2") (pinfunction "2_2") (pintype "passive"))
      (node (ref "RST") (pin "TP") (pinfunction "TP_TP") (pintype "input"))
      (node (ref "U2") (pin "3") (pinfunction "P10.3UCB3SOMI/UCB3SCL_3") (pintype "power_in"))
    )
    (net (code "24") (name "/AVCC") (class "Default")
      (node (ref "C16") (pin "1") (pinfunction "1_1") (pintype "passive"))
      (node (ref "C20") (pin "1") (pinfunction "1_1") (pintype "passive"))
      (node (ref "R13") (pin "1") (pinfunction "1_1") (pintype "passive"))
      (node (ref "U2") (pin "45") (pinfunction "AVCC1_45") (pintype "power_in"))
      (node (ref "U2") (pin "87") (pinfunction "AVCC2_87") (pintype "power_in"))
    )
    (net (code "25") (name "/CURR_SENSE_EN") (class "Default")
      (node (ref "C24") (pin "2") (pinfunction "2_2") (pintype "passive"))
      (node (ref "C25") (pin "2") (pinfunction "2_2") (pintype "passive"))
      (node (ref "C27") (pin "2") (pinfunction "2_2") (pintype "passive"))
      (node (ref "C30") (pin "2") (pinfunction "2_2") (pintype "passive"))
      (node (ref "U10") (pin "3") (pinfunction "VCC_3") (pintype "bidirectional"))
      (node (ref "U2") (pin "50") (pinfunction "P8.6/A19_50") (pintype "power_in"))
      (node (ref "U3") (pin "1") (pinfunction "IN_1") (pintype "input"))
      (node (ref "U7") (pin "3") (pinfunction "VCC_3") (pintype "bidirectional"))
      (node (ref "U8") (pin "3") (pinfunction "VCC_3") (pintype "bidirectional"))
      (node (ref "U9") (pin "3") (pinfunction "VCC_3") (pintype "bidirectional"))
    )
    (net (code "26") (name "/EXT_LIGHTNING_INT") (class "Default")
      (node (ref "JP2") (pin "2") (pinfunction "2_2") (pintype "passive"))
      (node (ref "U2") (pin "8") (pinfunction "P1.4/UCB0STE_8") (pintype "power_in"))
    )
    (net (code "27") (name "/EXT_UV_EN") (class "Default")
      (node (ref "JP2") (pin "1") (pinfunction "1_1") (pintype "passive"))
      (node (ref "U2") (pin "9") (pinfunction "P1.5/UCB0CLK_9") (pintype "power_in"))
    )
    (net (code "28") (name "/LORA_RST_N") (class "Default")
      (node (ref "LORA_RST_N") (pin "1") (pinfunction "1_1") (pintype "passive"))
      (node (ref "R12") (pin "1") (pinfunction "1_1") (pintype "passive"))
      (node (ref "U100") (pin "P$32") (pinfunction "P$32_P$32") (pintype "bidirectional"))
    )
    (net (code "29") (name "/M5OUT1") (class "Default")
      (node (ref "RS1") (pin "I1") (pinfunction "I1_I1") (pintype "bidirectional"))
      (node (ref "U4") (pin "2") (pinfunction "AOUT1_2") (pintype "output"))
    )
    (net (code "30") (name "/P1.0") (class "Default")
      (node (ref "DIGITAL_IO1") (pin "19") (pinfunction "19_19") (pintype "passive"))
      (node (ref "U2") (pin "4") (pinfunction "P1.0/UCA0STE_4") (pintype "power_in"))
    )
    (net (code "31") (name "/P2.1") (class "Default")
      (node (ref "DIGITAL_IO2") (pin "8") (pinfunction "8_8") (pintype "passive"))
      (node (ref "U2") (pin "17") (pinfunction "P2.1/PM_UCA1CLK_17") (pintype "power_in"))
    )
    (net (code "32") (name "/P2.4") (class "Default")
      (node (ref "DIGITAL_IO2") (pin "2") (pinfunction "2_2") (pintype "passive"))
      (node (ref "U2") (pin "20") (pinfunction "P2.4/PM_TA0.1_20") (pintype "power_in"))
    )
    (net (code "33") (name "/P2.5") (class "Default")
      (node (ref "DIGITAL_IO2") (pin "1") (pinfunction "1_1") (pintype "passive"))
      (node (ref "U2") (pin "21") (pinfunction "P2.5/PM_TA0.2_21") (pintype "power_in"))
    )
    (net (code "34") (name "/P2.6") (class "Default")
      (node (ref "DIGITAL_IO2") (pin "4") (pinfunction "4_4") (pintype "passive"))
      (node (ref "U2") (pin "22") (pinfunction "P2.6/PM_TA0.3_22") (pintype "power_in"))
    )
    (net (code "35") (name "/P2.7") (class "Default")
      (node (ref "DIGITAL_IO2") (pin "3") (pinfunction "3_3") (pintype "passive"))
      (node (ref "U2") (pin "23") (pinfunction "P2.7/PM_TA0.4_23") (pintype "power_in"))
    )
    (net (code "36") (name "/P5.6") (class "Default")
      (node (ref "DIGITAL_IO1") (pin "6") (pinfunction "6_6") (pintype "passive"))
      (node (ref "U2") (pin "70") (pinfunction "P5.6/TA2.1/VREF+/VEREF+/C1.7_70") (pintype "power_in"))
    )
    (net (code "37") (name "/P5.7") (class "Default")
      (node (ref "DIGITAL_IO1") (pin "5") (pinfunction "5_5") (pintype "passive"))
      (node (ref "U2") (pin "71") (pinfunction "P5.7/TA2.2/VREF-/VEREF-/C1.6_71") (pintype "power_in"))
    )
    (net (code "38") (name "/P6.6") (class "Default")
      (node (ref "DIGITAL_IO1") (pin "8") (pinfunction "8_8") (pintype "passive"))
      (node (ref "U2") (pin "80") (pinfunction "P6.6/TA2.3/UCB3SIMO/UCB3SDA/C1.1_80") (pintype "power_in"))
    )
    (net (code "39") (name "/P6.7") (class "Default")
      (node (ref "DIGITAL_IO1") (pin "7") (pinfunction "7_7") (pintype "passive"))
      (node (ref "U2") (pin "81") (pinfunction "P6.7/TA2.4/UCB3SOMI/UCB3SCL/C1.0_81") (pintype "power_in"))
    )
    (net (code "40") (name "/P7.0") (class "Default")
      (node (ref "DIGITAL_IO1") (pin "12") (pinfunction "12_12") (pintype "passive"))
      (node (ref "U2") (pin "88") (pinfunction "P7.0/PM_SMCLK/PM_DMAE0_88") (pintype "power_in"))
    )
    (net (code "41") (name "/P7.1") (class "Default")
      (node (ref "DIGITAL_IO1") (pin "11") (pinfunction "11_11") (pintype "passive"))
      (node (ref "U2") (pin "89") (pinfunction "P7.1/PM_C0OUT/PM_TA0CLK_89") (pintype "power_in"))
    )
    (net (code "42") (name "/P7.2") (class "Default")
      (node (ref "DIGITAL_IO1") (pin "14") (pinfunction "14_14") (pintype "passive"))
      (node (ref "U2") (pin "90") (pinfunction "P7.2/PM_C1OUT/PM_TA1CLK_90") (pintype "power_in"))
    )
    (net (code "43") (name "/P7.3") (class "Default")
      (node (ref "DIGITAL_IO1") (pin "13") (pinfunction "13_13") (pintype "passive"))
      (node (ref "U2") (pin "91") (pinfunction "P7.3/PM_TA0.0_91") (pintype "power_in"))
    )
    (net (code "44") (name "/P7.4") (class "Default")
      (node (ref "DIGITAL_IO2") (pin "7") (pinfunction "7_7") (pintype "passive"))
      (node (ref "U2") (pin "26") (pinfunction "P7.4/PM_TA1.4/C0.5_26") (pintype "power_in"))
    )
    (net (code "45") (name "/P7.5") (class "Default")
      (node (ref "DIGITAL_IO2") (pin "10") (pinfunction "10_10") (pintype "passive"))
      (node (ref "U2") (pin "27") (pinfunction "P7.5/PM_TA1.3/C0.4_27") (pintype "power_in"))
    )
    (net (code "46") (name "/P7.6") (class "Default")
      (node (ref "DIGITAL_IO2") (pin "9") (pinfunction "9_9") (pintype "passive"))
      (node (ref "U2") (pin "28") (pinfunction "P7.6/PM_TA1.2/C0.3_28") (pintype "power_in"))
    )
    (net (code "47") (name "/P9.2") (class "Default")
      (node (ref "DIGITAL_IO1") (pin "4") (pinfunction "4_4") (pintype "passive"))
      (node (ref "U2") (pin "74") (pinfunction "P9.2/TA3.3_74") (pintype "power_in"))
    )
    (net (code "48") (name "/P9.3") (class "Default")
      (node (ref "DIGITAL_IO1") (pin "3") (pinfunction "3_3") (pintype "passive"))
      (node (ref "U2") (pin "75") (pinfunction "P9.3/TA3.4_75") (pintype "power_in"))
    )
    (net (code "49") (name "/P9.4") (class "Default")
      (node (ref "DIGITAL_IO1") (pin "18") (pinfunction "18_18") (pintype "passive"))
      (node (ref "U2") (pin "96") (pinfunction "P9.4/UCA3STE_96") (pintype "power_in"))
    )
    (net (code "50") (name "/P9.5") (class "Default")
      (node (ref "DIGITAL_IO1") (pin "17") (pinfunction "17_17") (pintype "passive"))
      (node (ref "U2") (pin "97") (pinfunction "P9.5/UCA3CLK_97") (pintype "power_in"))
    )
    (net (code "51") (name "/P10.2") (class "Default")
      (node (ref "DIGITAL_IO1") (pin "20") (pinfunction "20_20") (pintype "passive"))
      (node (ref "U2") (pin "2") (pinfunction "P10.2/UCB3SIMO/UCB3SDA_2") (pintype "power_in"))
    )
    (net (code "52") (name "/P10.4") (class "Default")
      (node (ref "DIGITAL_IO2") (pin "6") (pinfunction "6_6") (pintype "passive"))
      (node (ref "U2") (pin "24") (pinfunction "P10.4/TA3.0/C0.7_24") (pintype "power_in"))
    )
    (net (code "53") (name "/P10.5") (class "Default")
      (node (ref "DIGITAL_IO2") (pin "5") (pinfunction "5_5") (pintype "passive"))
      (node (ref "U2") (pin "25") (pinfunction "P10.5/TA3.1/C0.6_25") (pintype "power_in"))
    )
    (net (code "54") (name "/PJ.2") (class "Default")
      (node (ref "DIGITAL_IO1") (pin "10") (pinfunction "10_10") (pintype "passive"))
      (node (ref "U2") (pin "85") (pinfunction "PJ.2/HFXOUT_85") (pintype "power_in"))
    )
    (net (code "55") (name "/PJ.3") (class "Default")
      (node (ref "DIGITAL_IO1") (pin "9") (pinfunction "9_9") (pintype "passive"))
      (node (ref "U2") (pin "86") (pinfunction "PJ.3/HFXIN_86") (pintype "power_in"))
    )
    (net (code "56") (name "/PJ.4") (class "Default")
      (node (ref "DIGITAL_IO1") (pin "16") (pinfunction "16_16") (pintype "passive"))
      (node (ref "U2") (pin "92") (pinfunction "PJ.4/TDI/ADC14CLK_92") (pintype "power_in"))
    )
    (net (code "57") (name "/PJ.5") (class "Default")
      (node (ref "DIGITAL_IO1") (pin "15") (pinfunction "15_15") (pintype "passive"))
      (node (ref "U2") (pin "93") (pinfunction "PJ.5/TDO/SWO_93") (pintype "power_in"))
    )
    (net (code "58") (name "/RST_N") (class "Default")
      (node (ref "C11") (pin "2") (pinfunction "2_2") (pintype "passive"))
      (node (ref "PROG") (pin "4") (pinfunction "4_4") (pintype "passive"))
      (node (ref "R9") (pin "2") (pinfunction "2_2") (pintype "passive"))
      (node (ref "U2") (pin "83") (pinfunction "RSTN/NMI_83") (pintype "power_in"))
    )
    (net (code "59") (name "/RX0") (class "Default")
      (node (ref "PROG") (pin "3") (pinfunction "3_3") (pintype "passive"))
      (node (ref "U2") (pin "6") (pinfunction "P1.2/UCA0RXD/UCA0SOMI_6") (pintype "power_in"))
    )
    (net (code "60") (name "/RX2") (class "Default")
      (node (ref "RX2/TX2") (pin "3") (pinfunction "3_3") (pintype "passive"))
      (node (ref "U2") (pin "34") (pinfunction "P3.2/PM_UCA2RXD/PM_UCA2SOMI_34") (pintype "power_in"))
    )
    (net (code "61") (name "/RX3") (class "Default")
      (node (ref "U100") (pin "P$6") (pinfunction "P$6_P$6") (pintype "bidirectional"))
      (node (ref "U2") (pin "98") (pinfunction "P9.6/UCA3RXD/UCA3SOMI_98") (pintype "power_in"))
    )
    (net (code "62") (name "/SCL") (class "Default")
      (node (ref "IC1") (pin "19") (pinfunction "COM1_19") (pintype "bidirectional"))
      (node (ref "IC2") (pin "4") (pinfunction "SCK_4") (pintype "bidirectional"))
      (node (ref "JP2") (pin "5") (pinfunction "5_5") (pintype "passive"))
      (node (ref "JP2") (pin "7") (pinfunction "7_7") (pintype "passive"))
      (node (ref "R2") (pin "1") (pinfunction "1_1") (pintype "passive"))
      (node (ref "U2") (pin "11") (pinfunction "P1.7/UCB0SOMI/UCB0SCL_11") (pintype "power_in"))
    )
    (net (code "63") (name "/SDA") (class "Default")
      (node (ref "IC1") (pin "20") (pinfunction "COM0_20") (pintype "bidirectional"))
      (node (ref "IC2") (pin "3") (pinfunction "SDI_3") (pintype "bidirectional"))
      (node (ref "JP2") (pin "6") (pinfunction "6_6") (pintype "passive"))
      (node (ref "JP2") (pin "8") (pinfunction "8_8") (pintype "passive"))
      (node (ref "R3") (pin "1") (pinfunction "1_1") (pintype "passive"))
      (node (ref "U2") (pin "10") (pinfunction "P1.6/UCB0SIMO/UCB0SDA_10") (pintype "power_in"))
    )
    (net (code "64") (name "/SPI_EXTSLAVE_TE") (class "Default")
      (node (ref "SPI") (pin "1") (pinfunction "1_1") (pintype "passive"))
      (node (ref "U2") (pin "76") (pinfunction "P6.2/UCB1STE/C1.5_76") (pintype "power_in"))
    )
    (net (code "65") (name "/SPI_FLASH_CS") (class "Default")
      (node (ref "R18") (pin "1") (pinfunction "1_1") (pintype "passive"))
      (node (ref "U2") (pin "69") (pinfunction "P5.5/A0_69") (pintype "power_in"))
      (node (ref "U6") (pin "CE") (pinfunction "CS_CE") (pintype "bidirectional"))
    )
    (net (code "66") (name "/SPI_MISO") (class "Default")
      (node (ref "SPI") (pin "2") (pinfunction "2_2") (pintype "passive"))
      (node (ref "U2") (pin "79") (pinfunction "P6.5/UCB1SOMI/UCB1SCL/C1.2_79") (pintype "power_in"))
      (node (ref "U6") (pin "SO") (pinfunction "MISO_SO") (pintype "bidirectional"))
    )
    (net (code "67") (name "/SPI_MOSI") (class "Default")
      (node (ref "SPI") (pin "4") (pinfunction "4_4") (pintype "passive"))
      (node (ref "U2") (pin "78") (pinfunction "P6.4/UCB1SIMO/UCB1SDA/C1.3_78") (pintype "power_in"))
      (node (ref "U6") (pin "SI") (pinfunction "MOSI_SI") (pintype "bidirectional"))
    )
    (net (code "68") (name "/SPI_SCK") (class "Default")
      (node (ref "SPI") (pin "3") (pinfunction "3_3") (pintype "passive"))
      (node (ref "U2") (pin "77") (pinfunction "P6.3/UCB1CLK/C1.4_77") (pintype "power_in"))
      (node (ref "U6") (pin "SCK") (pinfunction "SCK_SCK") (pintype "bidirectional"))
    )
    (net (code "69") (name "/TX0") (class "Default")
      (node (ref "PROG") (pin "2") (pinfunction "2_2") (pintype "passive"))
      (node (ref "U2") (pin "7") (pinfunction "P1.3/UCA0TXD/UCA0SIMO_7") (pintype "power_in"))
    )
    (net (code "70") (name "/TX2") (class "Default")
      (node (ref "RX2/TX2") (pin "2") (pinfunction "2_2") (pintype "passive"))
      (node (ref "U2") (pin "35") (pinfunction "P3.3/PM_UCA2TXD/PM_UCA2SIMO_35") (pintype "power_in"))
    )
    (net (code "71") (name "/TX3") (class "Default")
      (node (ref "U100") (pin "P$7") (pinfunction "P$7_P$7") (pintype "bidirectional"))
      (node (ref "U2") (pin "99") (pinfunction "P9.7/UCA3TXD/UCA3SIMO_99") (pintype "power_in"))
    )
    (net (code "72") (name "/VREF_M") (class "Default")
      (node (ref "U10") (pin "1") (pinfunction "REF_1") (pintype "bidirectional"))
      (node (ref "U3") (pin "2") (pinfunction "OUT_2") (pintype "output"))
      (node (ref "U7") (pin "1") (pinfunction "REF_1") (pintype "bidirectional"))
      (node (ref "U8") (pin "1") (pinfunction "REF_1") (pintype "bidirectional"))
      (node (ref "U9") (pin "1") (pinfunction "REF_1") (pintype "bidirectional"))
    )
    (net (code "73") (name "/V_MOTOR") (class "Default")
      (node (ref "C33") (pin "2") (pinfunction "2_2") (pintype "passive"))
      (node (ref "C34") (pin "2") (pinfunction "2_2") (pintype "passive"))
      (node (ref "U11") (pin "1") (pinfunction "VCC_1") (pintype "power_in"))
      (node (ref "U12") (pin "1") (pinfunction "VCC_1") (pintype "power_in"))
      (node (ref "VMOT_SEL") (pin "2") (pinfunction "2_2") (pintype "passive"))
    )
    (net (code "74") (name "/V_MOTOR2") (class "Default")
      (node (ref "C23") (pin "2") (pinfunction "2_2") (pintype "passive"))
      (node (ref "C26") (pin "2") (pinfunction "2_2") (pintype "passive"))
      (node (ref "U4") (pin "1") (pinfunction "VCC_1") (pintype "power_in"))
      (node (ref "U5") (pin "1") (pinfunction "VCC_1") (pintype "power_in"))
      (node (ref "VMOT_SEL100") (pin "2") (pinfunction "2_2") (pintype "passive"))
      (node (ref "V_MOT1") (pin "2") (pinfunction "2_2") (pintype "passive"))
    )
    (net (code "75") (name "/V_MOTOR_ALT") (class "Default")
      (node (ref "VMOT_SEL") (pin "3") (pinfunction "3_3") (pintype "passive"))
      (node (ref "V_MOT2") (pin "2") (pinfunction "2_2") (pintype "passive"))
    )
    (net (code "76") (name "5VEN") (class "Default")
      (node (ref "R1") (pin "1") (pinfunction "1_1") (pintype "passive"))
      (node (ref "U1") (pin "9") (pinfunction "EN_9") (pintype "input"))
      (node (ref "U2") (pin "16") (pinfunction "P2.0/PM_UCA1STE_16") (pintype "power_in"))
    )
    (net (code "77") (name "AGND") (class "Default")
      (node (ref "ANALOG") (pin "2") (pinfunction "2_2") (pintype "passive"))
      (node (ref "C16") (pin "2") (pinfunction "2_2") (pintype "passive"))
      (node (ref "C20") (pin "2") (pinfunction "2_2") (pintype "passive"))
      (node (ref "C24") (pin "1") (pinfunction "1_1") (pintype "passive"))
      (node (ref "C25") (pin "1") (pinfunction "1_1") (pintype "passive"))
      (node (ref "C27") (pin "1") (pinfunction "1_1") (pintype "passive"))
      (node (ref "C28") (pin "1") (pinfunction "1_1") (pintype "passive"))
      (node (ref "C29") (pin "1") (pinfunction "1_1") (pintype "passive"))
      (node (ref "C30") (pin "1") (pinfunction "1_1") (pintype "passive"))
      (node (ref "C31") (pin "1") (pinfunction "1_1") (pintype "passive"))
      (node (ref "C32") (pin "1") (pinfunction "1_1") (pintype "passive"))
      (node (ref "R14") (pin "2") (pinfunction "2_2") (pintype "passive"))
      (node (ref "U$2") (pin "AGND") (pinfunction "AGND_AGND") (pintype "output"))
      (node (ref "U10") (pin "2") (pinfunction "GND_2") (pintype "bidirectional"))
      (node (ref "U2") (pin "40") (pinfunction "AVSS3_40") (pintype "power_in"))
      (node (ref "U2") (pin "43") (pinfunction "AVSS1_43") (pintype "power_in"))
      (node (ref "U2") (pin "84") (pinfunction "AVSS2_84") (pintype "power_in"))
      (node (ref "U3") (pin "3") (pinfunction "GND_3") (pintype "power_in"))
      (node (ref "U7") (pin "2") (pinfunction "GND_2") (pintype "bidirectional"))
      (node (ref "U8") (pin "2") (pinfunction "GND_2") (pintype "bidirectional"))
      (node (ref "U9") (pin "2") (pinfunction "GND_2") (pintype "bidirectional"))
    )
    (net (code "78") (name "GND") (class "Default")
      (node (ref "868MHZ") (pin "GND@1") (pinfunction "GND4_GND@1") (pintype "power_in"))
      (node (ref "868MHZ") (pin "GND@2") (pinfunction "GND3_GND@2") (pintype "power_in"))
      (node (ref "868MHZ") (pin "GND@3") (pinfunction "GND2_GND@3") (pintype "power_in"))
      (node (ref "868MHZ") (pin "GND@4") (pinfunction "GND1_GND@4") (pintype "power_in"))
      (node (ref "C1") (pin "2") (pinfunction "2_2") (pintype "passive"))
      (node (ref "C10") (pin "2") (pinfunction "2_2") (pintype "passive"))
      (node (ref "C11") (pin "1") (pinfunction "1_1") (pintype "passive"))
      (node (ref "C12") (pin "-") (pinfunction "-_-") (pintype "passive"))
      (node (ref "C13") (pin "1") (pinfunction "1_1") (pintype "passive"))
      (node (ref "C14") (pin "1") (pinfunction "1_1") (pintype "passive"))
      (node (ref "C15") (pin "-") (pinfunction "-_-") (pintype "passive"))
      (node (ref "C17") (pin "2") (pinfunction "2_2") (pintype "passive"))
      (node (ref "C18") (pin "1") (pinfunction "1_1") (pintype "passive"))
      (node (ref "C19") (pin "1") (pinfunction "1_1") (pintype "passive"))
      (node (ref "C2") (pin "1") (pinfunction "1_1") (pintype "passive"))
      (node (ref "C21") (pin "1") (pinfunction "1_1") (pintype "passive"))
      (node (ref "C22") (pin "2") (pinfunction "2_2") (pintype "passive"))
      (node (ref "C23") (pin "1") (pinfunction "1_1") (pintype "passive"))
      (node (ref "C26") (pin "1") (pinfunction "1_1") (pintype "passive"))
      (node (ref "C3") (pin "2") (pinfunction "2_2") (pintype "passive"))
      (node (ref "C33") (pin "1") (pinfunction "1_1") (pintype "passive"))
      (node (ref "C34") (pin "1") (pinfunction "1_1") (pintype "passive"))
      (node (ref "C4") (pin "2") (pinfunction "2_2") (pintype "passive"))
      (node (ref "C5") (pin "2") (pinfunction "2_2") (pintype "passive"))
      (node (ref "C6") (pin "2") (pinfunction "2_2") (pintype "passive"))
      (node (ref "C7") (pin "2") (pinfunction "2_2") (pintype "passive"))
      (node (ref "C8") (pin "2") (pinfunction "2_2") (pintype "passive"))
      (node (ref "C9") (pin "2") (pinfunction "2_2") (pintype "passive"))
      (node (ref "DIGITAL_IO1") (pin "2") (pinfunction "2_2") (pintype "passive"))
      (node (ref "DIGITAL_IO1") (pin "22") (pinfunction "22_22") (pintype "passive"))
      (node (ref "IC1") (pin "10") (pinfunction "PIN10_10") (pintype "bidirectional"))
      (node (ref "IC1") (pin "15") (pinfunction "PIN15_15") (pintype "bidirectional"))
      (node (ref "IC1") (pin "16") (pinfunction "PIN16_16") (pintype "bidirectional"))
      (node (ref "IC1") (pin "17") (pinfunction "COM3_17") (pintype "bidirectional"))
      (node (ref "IC1") (pin "18") (pinfunction "COM2_18") (pintype "bidirectional"))
      (node (ref "IC1") (pin "2") (pinfunction "GND_2") (pintype "bidirectional"))
      (node (ref "IC1") (pin "25") (pinfunction "GNDIO_25") (pintype "bidirectional"))
      (node (ref "IC1") (pin "5") (pinfunction "PS1_5") (pintype "bidirectional"))
      (node (ref "IC1") (pin "6") (pinfunction "PS0_6") (pintype "bidirectional"))
      (node (ref "IC2") (pin "1") (pinfunction "GND_1") (pintype "power_in"))
      (node (ref "IC2") (pin "5") (pinfunction "SDO_5") (pintype "input"))
      (node (ref "IC2") (pin "7") (pinfunction "GND_7") (pintype "power_in"))
      (node (ref "JP1") (pin "1") (pinfunction "1_1") (pintype "passive"))
      (node (ref "JP1") (pin "2") (pinfunction "2_2") (pintype "passive"))
      (node (ref "JP1") (pin "3") (pinfunction "3_3") (pintype "passive"))
      (node (ref "JP1") (pin "4") (pinfunction "4_4") (pintype "passive"))
      (node (ref "JP1") (pin "7") (pinfunction "7_7") (pintype "passive"))
      (node (ref "JP1") (pin "8") (pinfunction "8_8") (pintype "passive"))
      (node (ref "JP2") (pin "4") (pinfunction "4_4") (pintype "passive"))
      (node (ref "JP3") (pin "2") (pinfunction "2_2") (pintype "passive"))
      (node (ref "JP3") (pin "4") (pinfunction "4_4") (pintype "passive"))
      (node (ref "LED33_J") (pin "1") (pinfunction "1_1") (pintype "passive"))
      (node (ref "LED5_J") (pin "1") (pinfunction "1_1") (pintype "passive"))
      (node (ref "PROG") (pin "1") (pinfunction "1_1") (pintype "passive"))
      (node (ref "Q2") (pin "P3") (pinfunction "GND_P3") (pintype "power_in"))
      (node (ref "R10") (pin "1") (pinfunction "1_1") (pintype "passive"))
      (node (ref "R11") (pin "1") (pinfunction "1_1") (pintype "passive"))
      (node (ref "RX1/TX1") (pin "1") (pinfunction "1_1") (pintype "passive"))
      (node (ref "RX2/TX2") (pin "1") (pinfunction "1_1") (pintype "passive"))
      (node (ref "U$2") (pin "DGND") (pinfunction "DGND_DGND") (pintype "output"))
      (node (ref "U$2") (pin "GND") (pinfunction "GND_GND") (pintype "power_in"))
      (node (ref "U1") (pin "EXPAD") (pinfunction "GND_EXPAD") (pintype "power_in"))
      (node (ref "U1") (pin "GND1") (pinfunction "GND1_GND1") (pintype "power_in"))
      (node (ref "U1") (pin "GND2") (pinfunction "GND2_GND2") (pintype "power_in"))
      (node (ref "U1") (pin "GND3") (pinfunction "GND3_GND3") (pintype "power_in"))
      (node (ref "U1") (pin "GND4") (pinfunction "GND4_GND4") (pintype "power_in"))
      (node (ref "U1") (pin "GND5") (pinfunction "GND5_GND5") (pintype "power_in"))
      (node (ref "U100") (pin "P$1") (pinfunction "P$1_P$1") (pintype "bidirectional"))
      (node (ref "U100") (pin "P$11") (pinfunction "P$11_P$11") (pintype "bidirectional"))
      (node (ref "U100") (pin "P$20") (pinfunction "P$20_P$20") (pintype "bidirectional"))
      (node (ref "U100") (pin "P$21") (pinfunction "P$21_P$21") (pintype "bidirectional"))
      (node (ref "U100") (pin "P$22") (pinfunction "P$22_P$22") (pintype "bidirectional"))
      (node (ref "U100") (pin "P$24") (pinfunction "P$24_P$24") (pintype "bidirectional"))
      (node (ref "U100") (pin "P$26") (pinfunction "P$26_P$26") (pintype "bidirectional"))
      (node (ref "U100") (pin "P$27") (pinfunction "P$27_P$27") (pintype "bidirectional"))
      (node (ref "U100") (pin "P$28") (pinfunction "P$28_P$28") (pintype "bidirectional"))
      (node (ref "U100") (pin "P$33") (pinfunction "P$33_P$33") (pintype "bidirectional"))
      (node (ref "U100") (pin "P$41") (pinfunction "P$41_P$41") (pintype "bidirectional"))
      (node (ref "U100") (pin "P$47") (pinfunction "P$47_P$47") (pintype "bidirectional"))
      (node (ref "U100") (pin "P$8") (pinfunction "P$8_P$8") (pintype "bidirectional"))
      (node (ref "U11") (pin "13") (pinfunction "EPAD_13") (pintype "passive"))
      (node (ref "U11") (pin "6") (pinfunction "GND_6") (pintype "passive"))
      (node (ref "U12") (pin "13") (pinfunction "EPAD_13") (pintype "passive"))
      (node (ref "U12") (pin "6") (pinfunction "GND_6") (pintype "passive"))
      (node (ref "U2") (pin "15") (pinfunction "DVSS1_15") (pintype "power_in"))
      (node (ref "U2") (pin "72") (pinfunction "DVSS2_72") (pintype "power_in"))
      (node (ref "U2") (pin "82") (pinfunction "DVSS3_82") (pintype "power_in"))
      (node (ref "U4") (pin "13") (pinfunction "EPAD_13") (pintype "passive"))
      (node (ref "U4") (pin "6") (pinfunction "GND_6") (pintype "passive"))
      (node (ref "U5") (pin "13") (pinfunction "EPAD_13") (pintype "passive"))
      (node (ref "U5") (pin "6") (pinfunction "GND_6") (pintype "passive"))
      (node (ref "U6") (pin "VSS") (pinfunction "GND_VSS") (pintype "bidirectional"))
      (node (ref "V_MOT1") (pin "1") (pinfunction "1_1") (pintype "passive"))
      (node (ref "V_MOT2") (pin "1") (pinfunction "1_1") (pintype "passive"))
    )
    (net (code "79") (name "LED0") (class "Default")
      (node (ref "LED2") (pin "A") (pinfunction "A_A") (pintype "passive"))
      (node (ref "U2") (pin "100") (pinfunction "P10.0/UCB3STE_100") (pintype "power_in"))
    )
    (net (code "80") (name "LED1") (class "Default")
      (node (ref "LED1") (pin "A") (pinfunction "A_A") (pintype "passive"))
      (node (ref "U2") (pin "1") (pinfunction "P10.1/UCB3CLK_1") (pintype "power_in"))
    )
    (net (code "81") (name "M1IN1") (class "Default")
      (node (ref "U11") (pin "10") (pinfunction "AIN1_/_APHASE_10") (pintype "input"))
      (node (ref "U2") (pin "52") (pinfunction "P9.0/A17_52") (pintype "power_in"))
    )
    (net (code "82") (name "M1IN2") (class "Default")
      (node (ref "U11") (pin "9") (pinfunction "AIN2_/_AENBL_9") (pintype "input"))
      (node (ref "U2") (pin "53") (pinfunction "P9.1/A16_53") (pintype "power_in"))
    )
    (net (code "83") (name "M2IN1") (class "Default")
      (node (ref "U11") (pin "8") (pinfunction "BIN1_/_BPHASE_8") (pintype "input"))
      (node (ref "U2") (pin "54") (pinfunction "P6.0/A15_54") (pintype "power_in"))
    )
    (net (code "84") (name "M2IN2") (class "Default")
      (node (ref "U11") (pin "7") (pinfunction "BIN2_/_BENBL_7") (pintype "input"))
      (node (ref "U2") (pin "55") (pinfunction "P6.1/A14_55") (pintype "power_in"))
    )
    (net (code "85") (name "M3IN1") (class "Default")
      (node (ref "U12") (pin "10") (pinfunction "AIN1_/_APHASE_10") (pintype "input"))
      (node (ref "U2") (pin "56") (pinfunction "P4.0/A13_56") (pintype "power_in"))
    )
    (net (code "86") (name "M3IN2") (class "Default")
      (node (ref "U12") (pin "9") (pinfunction "AIN2_/_AENBL_9") (pintype "input"))
      (node (ref "U2") (pin "57") (pinfunction "P4.1/A12_57") (pintype "power_in"))
    )
    (net (code "87") (name "M4IN1") (class "Default")
      (node (ref "U12") (pin "8") (pinfunction "BIN1_/_BPHASE_8") (pintype "input"))
      (node (ref "U2") (pin "58") (pinfunction "P4.2/ACLK/TA2CLK/A11_58") (pintype "power_in"))
    )
    (net (code "88") (name "M4IN2") (class "Default")
      (node (ref "U12") (pin "7") (pinfunction "BIN2_/_BENBL_7") (pintype "input"))
      (node (ref "U2") (pin "59") (pinfunction "P4.3/MCLK/RTCCLK/A10_59") (pintype "power_in"))
    )
    (net (code "89") (name "M5IN1") (class "Default")
      (node (ref "U2") (pin "29") (pinfunction "P7.7/PM_TA1.1/C0.2_29") (pintype "power_in"))
      (node (ref "U4") (pin "10") (pinfunction "AIN1_/_APHASE_10") (pintype "input"))
    )
    (net (code "90") (name "M5IN2") (class "Default")
      (node (ref "U2") (pin "30") (pinfunction "P8.0/UCB3STE/TA1.0/C0.1_30") (pintype "power_in"))
      (node (ref "U4") (pin "9") (pinfunction "AIN2_/_AENBL_9") (pintype "input"))
    )
    (net (code "91") (name "M6IN1") (class "Default")
      (node (ref "U2") (pin "32") (pinfunction "P3.0/PM_UCA2STE_32") (pintype "power_in"))
      (node (ref "U4") (pin "8") (pinfunction "BIN1_/_BPHASE_8") (pintype "input"))
    )
    (net (code "92") (name "M6IN2") (class "Default")
      (node (ref "U2") (pin "31") (pinfunction "P8.1/UCB3CLK/TA2.0/C0.0_31") (pintype "power_in"))
      (node (ref "U4") (pin "7") (pinfunction "BIN2_/_BENBL_7") (pintype "input"))
    )
    (net (code "93") (name "M7IN1") (class "Default")
      (node (ref "U2") (pin "36") (pinfunction "P3.4/PM_UCB2STE_36") (pintype "power_in"))
      (node (ref "U5") (pin "10") (pinfunction "AIN1_/_APHASE_10") (pintype "input"))
    )
    (net (code "94") (name "M7IN2") (class "Default")
      (node (ref "U2") (pin "37") (pinfunction "P3.5/PM_UCB2CLK_37") (pintype "power_in"))
      (node (ref "U5") (pin "9") (pinfunction "AIN2_/_AENBL_9") (pintype "input"))
    )
    (net (code "95") (name "M8IN1") (class "Default")
      (node (ref "U2") (pin "38") (pinfunction "P3.6/PM_UCB2SIMO/PM_UCB2SDA_38") (pintype "power_in"))
      (node (ref "U5") (pin "8") (pinfunction "BIN1_/_BPHASE_8") (pintype "input"))
    )
    (net (code "96") (name "M8IN2") (class "Default")
      (node (ref "U2") (pin "39") (pinfunction "P3.7/PM_UCB2SOMI/PM_UCB2SCL_39") (pintype "power_in"))
      (node (ref "U5") (pin "7") (pinfunction "BIN2_/_BENBL_7") (pintype "input"))
    )
    (net (code "97") (name "M1234SLEEP") (class "Default")
      (node (ref "U11") (pin "11") (pinfunction "MODE_11") (pintype "input"))
      (node (ref "U11") (pin "12") (pinfunction "NSLEEP_12") (pintype "input"))
      (node (ref "U12") (pin "11") (pinfunction "MODE_11") (pintype "input"))
      (node (ref "U12") (pin "12") (pinfunction "NSLEEP_12") (pintype "input"))
      (node (ref "U2") (pin "51") (pinfunction "P8.7/A18_51") (pintype "power_in"))
    )
    (net (code "98") (name "M5678SLEEP") (class "Default")
      (node (ref "U2") (pin "33") (pinfunction "P3.1/PM_UCA2CLK_33") (pintype "power_in"))
      (node (ref "U4") (pin "11") (pinfunction "MODE_11") (pintype "input"))
      (node (ref "U4") (pin "12") (pinfunction "NSLEEP_12") (pintype "input"))
      (node (ref "U5") (pin "11") (pinfunction "MODE_11") (pintype "input"))
      (node (ref "U5") (pin "12") (pinfunction "NSLEEP_12") (pintype "input"))
    )
    (net (code "99") (name "Net-(3V-PadC)") (class "Default")
      (node (ref "3V") (pin "C") (pinfunction "C_C") (pintype "passive"))
      (node (ref "R8") (pin "2") (pinfunction "2_2") (pintype "passive"))
    )
    (net (code "100") (name "Net-(5V-PadC)") (class "Default")
      (node (ref "5V") (pin "C") (pinfunction "C_C") (pintype "passive"))
      (node (ref "R6") (pin "2") (pinfunction "2_2") (pintype "passive"))
    )
    (net (code "101") (name "Net-(868MHZ-ANT)") (class "Default")
      (node (ref "868MHZ") (pin "P") (pinfunction "ANT_P") (pintype "bidirectional"))
      (node (ref "U100") (pin "P$23") (pinfunction "P$23_P$23") (pintype "bidirectional"))
    )
    (net (code "102") (name "Net-(IC1-CAP)") (class "Default")
      (node (ref "C2") (pin "2") (pinfunction "2_2") (pintype "passive"))
      (node (ref "IC1") (pin "9") (pinfunction "CAP_9") (pintype "bidirectional"))
    )
    (net (code "103") (name "Net-(IC1-XIN32)") (class "Default")
      (node (ref "C5") (pin "1") (pinfunction "1_1") (pintype "passive"))
      (node (ref "IC1") (pin "27") (pinfunction "XIN32_27") (pintype "bidirectional"))
      (node (ref "Q1") (pin "2") (pinfunction "2_2") (pintype "passive"))
    )
    (net (code "104") (name "Net-(IC1-XOUT32)") (class "Default")
      (node (ref "C6") (pin "1") (pinfunction "1_1") (pintype "passive"))
      (node (ref "IC1") (pin "26") (pinfunction "XOUT32_26") (pintype "bidirectional"))
      (node (ref "Q1") (pin "1") (pinfunction "1_1") (pintype "passive"))
    )
    (net (code "105") (name "Net-(L1-2)") (class "Default")
      (node (ref "L1") (pin "P$2") (pinfunction "2_P$2") (pintype "passive"))
      (node (ref "U1") (pin "1") (pinfunction "SW_1") (pintype "power_in"))
      (node (ref "U1") (pin "2") (pinfunction "SW_2") (pintype "power_in"))
    )
    (net (code "106") (name "Net-(LED1-PadC)") (class "Default")
      (node (ref "LED1") (pin "C") (pinfunction "C_C") (pintype "passive"))
      (node (ref "R10") (pin "2") (pinfunction "2_2") (pintype "passive"))
    )
    (net (code "107") (name "Net-(LED2-PadC)") (class "Default")
      (node (ref "LED2") (pin "C") (pinfunction "C_C") (pintype "passive"))
      (node (ref "R11") (pin "2") (pinfunction "2_2") (pintype "passive"))
    )
    (net (code "108") (name "Net-(LED5_J-Pad2)") (class "Default")
      (node (ref "LED5_J") (pin "2") (pinfunction "2_2") (pintype "passive"))
      (node (ref "R6") (pin "1") (pinfunction "1_1") (pintype "passive"))
    )
    (net (code "109") (name "Net-(LED33_J-Pad2)") (class "Default")
      (node (ref "LED33_J") (pin "2") (pinfunction "2_2") (pintype "passive"))
      (node (ref "R8") (pin "1") (pinfunction "1_1") (pintype "passive"))
    )
    (net (code "110") (name "Net-(M5/M6-Pad1)") (class "Default")
      (node (ref "M5/M6") (pin "1") (pinfunction "1_1") (pintype "passive"))
      (node (ref "RS1") (pin "I2") (pinfunction "I2_I2") (pintype "bidirectional"))
    )
    (net (code "111") (name "Net-(M5/M6-Pad3)") (class "Default")
      (node (ref "M5/M6") (pin "3") (pinfunction "3_3") (pintype "passive"))
      (node (ref "RS2") (pin "I2") (pinfunction "I2_I2") (pintype "bidirectional"))
    )
    (net (code "112") (name "Net-(M7/M8-Pad1)") (class "Default")
      (node (ref "M7/M8") (pin "1") (pinfunction "1_1") (pintype "passive"))
      (node (ref "RS3") (pin "I2") (pinfunction "I2_I2") (pintype "bidirectional"))
    )
    (net (code "113") (name "Net-(M7/M8-Pad3)") (class "Default")
      (node (ref "M7/M8") (pin "3") (pinfunction "3_3") (pintype "passive"))
      (node (ref "RS4") (pin "I2") (pinfunction "I2_I2") (pintype "bidirectional"))
    )
    (net (code "114") (name "Net-(Q2-1)") (class "Default")
      (node (ref "C19") (pin "2") (pinfunction "2_2") (pintype "passive"))
      (node (ref "Q2") (pin "P1") (pinfunction "1_P1") (pintype "bidirectional"))
      (node (ref "U2") (pin "42") (pinfunction "PJ.1/LFXOUT_42") (pintype "power_in"))
    )
    (net (code "115") (name "Net-(Q2-2)") (class "Default")
      (node (ref "C18") (pin "2") (pinfunction "2_2") (pintype "passive"))
      (node (ref "Q2") (pin "P2") (pinfunction "2_P2") (pintype "bidirectional"))
      (node (ref "U2") (pin "41") (pinfunction "PJ.0/LFXIN_41") (pintype "power_in"))
    )
    (net (code "116") (name "Net-(U1-PG)") (class "Default")
      (node (ref "R7") (pin "1") (pinfunction "1_1") (pintype "passive"))
      (node (ref "U1") (pin "5") (pinfunction "PG_5") (pintype "output"))
    )
    (net (code "117") (name "Net-(U1-SS)") (class "Default")
      (node (ref "C10") (pin "1") (pinfunction "1_1") (pintype "passive"))
      (node (ref "U1") (pin "6") (pinfunction "SS_6") (pintype "bidirectional"))
    )
    (net (code "118") (name "Net-(U2-DCOR)") (class "Default")
      (node (ref "R14") (pin "1") (pinfunction "1_1") (pintype "passive"))
      (node (ref "U2") (pin "44") (pinfunction "DCOR_44") (pintype "power_in"))
    )
    (net (code "119") (name "Net-(U2-SWCLKTCK)") (class "Default")
      (node (ref "PROG") (pin "5") (pinfunction "5_5") (pintype "passive"))
      (node (ref "U2") (pin "95") (pinfunction "SWCLKTCK_95") (pintype "power_in"))
    )
    (net (code "120") (name "Net-(U2-SWDIOTMS)") (class "Default")
      (node (ref "PROG") (pin "6") (pinfunction "6_6") (pintype "passive"))
      (node (ref "U2") (pin "94") (pinfunction "SWDIOTMS_94") (pintype "power_in"))
    )
    (net (code "121") (name "Net-(U2-VCORE)") (class "Default")
      (node (ref "C14") (pin "2") (pinfunction "2_2") (pintype "passive"))
      (node (ref "C15") (pin "+") (pinfunction "+_+") (pintype "passive"))
      (node (ref "L2") (pin "1") (pinfunction "1_1") (pintype "passive"))
      (node (ref "U2") (pin "12") (pinfunction "VCORE_12") (pintype "power_in"))
    )
    (net (code "122") (name "Net-(U2-VSW)") (class "Default")
      (node (ref "L2") (pin "2") (pinfunction "2_2") (pintype "passive"))
      (node (ref "U2") (pin "14") (pinfunction "VSW_14") (pintype "power_in"))
    )
    (net (code "123") (name "Net-(U4-AOUT2)") (class "Default")
      (node (ref "M5/M6") (pin "2") (pinfunction "2_2") (pintype "passive"))
      (node (ref "U4") (pin "3") (pinfunction "AOUT2_3") (pintype "output"))
    )
    (net (code "124") (name "Net-(U4-BOUT1)") (class "Default")
      (node (ref "RS2") (pin "I1") (pinfunction "I1_I1") (pintype "bidirectional"))
      (node (ref "U4") (pin "4") (pinfunction "BOUT1_4") (pintype "output"))
    )
    (net (code "125") (name "Net-(U4-BOUT2)") (class "Default")
      (node (ref "M5/M6") (pin "4") (pinfunction "4_4") (pintype "passive"))
      (node (ref "U4") (pin "5") (pinfunction "BOUT2_5") (pintype "output"))
    )
    (net (code "126") (name "Net-(U5-AOUT1)") (class "Default")
      (node (ref "RS3") (pin "I1") (pinfunction "I1_I1") (pintype "bidirectional"))
      (node (ref "U5") (pin "2") (pinfunction "AOUT1_2") (pintype "output"))
    )
    (net (code "127") (name "Net-(U5-AOUT2)") (class "Default")
      (node (ref "M7/M8") (pin "2") (pinfunction "2_2") (pintype "passive"))
      (node (ref "U5") (pin "3") (pinfunction "AOUT2_3") (pintype "output"))
    )
    (net (code "128") (name "Net-(U5-BOUT1)") (class "Default")
      (node (ref "RS4") (pin "I1") (pinfunction "I1_I1") (pintype "bidirectional"))
      (node (ref "U5") (pin "4") (pinfunction "BOUT1_4") (pintype "output"))
    )
    (net (code "129") (name "Net-(U5-BOUT2)") (class "Default")
      (node (ref "M7/M8") (pin "4") (pinfunction "4_4") (pintype "passive"))
      (node (ref "U5") (pin "5") (pinfunction "BOUT2_5") (pintype "output"))
    )
    (net (code "130") (name "Net-(U7-IN+)") (class "Default")
      (node (ref "RS1") (pin "V1") (pinfunction "V1_V1") (pintype "bidirectional"))
      (node (ref "U7") (pin "4") (pinfunction "IN+_4") (pintype "bidirectional"))
    )
    (net (code "131") (name "Net-(U7-IN-)") (class "Default")
      (node (ref "RS1") (pin "V2") (pinfunction "V2_V2") (pintype "bidirectional"))
      (node (ref "U7") (pin "5") (pinfunction "IN-_5") (pintype "bidirectional"))
    )
    (net (code "132") (name "Net-(U8-IN+)") (class "Default")
      (node (ref "RS2") (pin "V1") (pinfunction "V1_V1") (pintype "bidirectional"))
      (node (ref "U8") (pin "4") (pinfunction "IN+_4") (pintype "bidirectional"))
    )
    (net (code "133") (name "Net-(U8-IN-)") (class "Default")
      (node (ref "RS2") (pin "V2") (pinfunction "V2_V2") (pintype "bidirectional"))
      (node (ref "U8") (pin "5") (pinfunction "IN-_5") (pintype "bidirectional"))
    )
    (net (code "134") (name "Net-(U9-IN+)") (class "Default")
      (node (ref "RS3") (pin "V1") (pinfunction "V1_V1") (pintype "bidirectional"))
      (node (ref "U9") (pin "4") (pinfunction "IN+_4") (pintype "bidirectional"))
    )
    (net (code "135") (name "Net-(U9-IN-)") (class "Default")
      (node (ref "RS3") (pin "V2") (pinfunction "V2_V2") (pintype "bidirectional"))
      (node (ref "U9") (pin "5") (pinfunction "IN-_5") (pintype "bidirectional"))
    )
    (net (code "136") (name "Net-(U10-IN+)") (class "Default")
      (node (ref "RS4") (pin "V1") (pinfunction "V1_V1") (pintype "bidirectional"))
      (node (ref "U10") (pin "4") (pinfunction "IN+_4") (pintype "bidirectional"))
    )
    (net (code "137") (name "Net-(U10-IN-)") (class "Default")
      (node (ref "RS4") (pin "V2") (pinfunction "V2_V2") (pintype "bidirectional"))
      (node (ref "U10") (pin "5") (pinfunction "IN-_5") (pintype "bidirectional"))
    )
    (net (code "138") (name "Net-(U11-AOUT1)") (class "Default")
      (node (ref "M1/M2") (pin "1") (pinfunction "1_1") (pintype "passive"))
      (node (ref "U11") (pin "2") (pinfunction "AOUT1_2") (pintype "output"))
    )
    (net (code "139") (name "Net-(U11-AOUT2)") (class "Default")
      (node (ref "M1/M2") (pin "2") (pinfunction "2_2") (pintype "passive"))
      (node (ref "U11") (pin "3") (pinfunction "AOUT2_3") (pintype "output"))
    )
    (net (code "140") (name "Net-(U11-BOUT1)") (class "Default")
      (node (ref "M1/M2") (pin "3") (pinfunction "3_3") (pintype "passive"))
      (node (ref "U11") (pin "4") (pinfunction "BOUT1_4") (pintype "output"))
    )
    (net (code "141") (name "Net-(U11-BOUT2)") (class "Default")
      (node (ref "M1/M2") (pin "4") (pinfunction "4_4") (pintype "passive"))
      (node (ref "U11") (pin "5") (pinfunction "BOUT2_5") (pintype "output"))
    )
    (net (code "142") (name "Net-(U12-AOUT1)") (class "Default")
      (node (ref "M3/M4") (pin "1") (pinfunction "1_1") (pintype "passive"))
      (node (ref "U12") (pin "2") (pinfunction "AOUT1_2") (pintype "output"))
    )
    (net (code "143") (name "Net-(U12-AOUT2)") (class "Default")
      (node (ref "M3/M4") (pin "2") (pinfunction "2_2") (pintype "passive"))
      (node (ref "U12") (pin "3") (pinfunction "AOUT2_3") (pintype "output"))
    )
    (net (code "144") (name "Net-(U12-BOUT1)") (class "Default")
      (node (ref "M3/M4") (pin "3") (pinfunction "3_3") (pintype "passive"))
      (node (ref "U12") (pin "4") (pinfunction "BOUT1_4") (pintype "output"))
    )
    (net (code "145") (name "Net-(U12-BOUT2)") (class "Default")
      (node (ref "M3/M4") (pin "4") (pinfunction "4_4") (pintype "passive"))
      (node (ref "U12") (pin "5") (pinfunction "BOUT2_5") (pintype "output"))
    )
    (net (code "146") (name "RX1") (class "Default")
      (node (ref "RX1/TX1") (pin "3") (pinfunction "3_3") (pintype "passive"))
      (node (ref "U2") (pin "18") (pinfunction "P2.2/PM_UCA1RXD/PM_UCA1SOMI_18") (pintype "power_in"))
    )
    (net (code "147") (name "TX1") (class "Default")
      (node (ref "RX1/TX1") (pin "2") (pinfunction "2_2") (pintype "passive"))
      (node (ref "U2") (pin "19") (pinfunction "P2.3/PM_UCA1TXD/PM_UCA1SIMO_19") (pintype "power_in"))
    )
    (net (code "148") (name "unconnected-(IC1-PIN1-Pad1)") (class "Default")
      (node (ref "IC1") (pin "1") (pinfunction "PIN1_1") (pintype "bidirectional"))
    )
    (net (code "149") (name "unconnected-(IC1-PIN7-Pad7)") (class "Default")
      (node (ref "IC1") (pin "7") (pinfunction "PIN7_7") (pintype "bidirectional"))
    )
    (net (code "150") (name "unconnected-(IC1-PIN8-Pad8)") (class "Default")
      (node (ref "IC1") (pin "8") (pinfunction "PIN8_8") (pintype "bidirectional"))
    )
    (net (code "151") (name "unconnected-(IC1-PIN12-Pad12)") (class "Default")
      (node (ref "IC1") (pin "12") (pinfunction "PIN12_12") (pintype "bidirectional"))
    )
    (net (code "152") (name "unconnected-(IC1-PIN13-Pad13)") (class "Default")
      (node (ref "IC1") (pin "13") (pinfunction "PIN13_13") (pintype "bidirectional"))
    )
    (net (code "153") (name "unconnected-(IC1-PIN21-Pad21)") (class "Default")
      (node (ref "IC1") (pin "21") (pinfunction "PIN21_21") (pintype "bidirectional"))
    )
    (net (code "154") (name "unconnected-(IC1-PIN22-Pad22)") (class "Default")
      (node (ref "IC1") (pin "22") (pinfunction "PIN22_22") (pintype "bidirectional"))
    )
    (net (code "155") (name "unconnected-(IC1-PIN23-Pad23)") (class "Default")
      (node (ref "IC1") (pin "23") (pinfunction "PIN23_23") (pintype "bidirectional"))
    )
    (net (code "156") (name "unconnected-(IC1-PIN24-Pad24)") (class "Default")
      (node (ref "IC1") (pin "24") (pinfunction "PIN24_24") (pintype "bidirectional"))
    )
    (net (code "157") (name "unconnected-(U1-HYS-Pad8)") (class "Default")
      (node (ref "U1") (pin "8") (pinfunction "HYS_8") (pintype "output"))
    )
    (net (code "158") (name "unconnected-(U100-PadP$25)") (class "Default")
      (node (ref "U100") (pin "P$25") (pinfunction "P$25_P$25") (pintype "bidirectional"))
    )
  )
)
